# SCH_Amiga-KickSmash-32-in-system-flash_2.net
KiCad netlist of a schematic drawn in EasyEDA
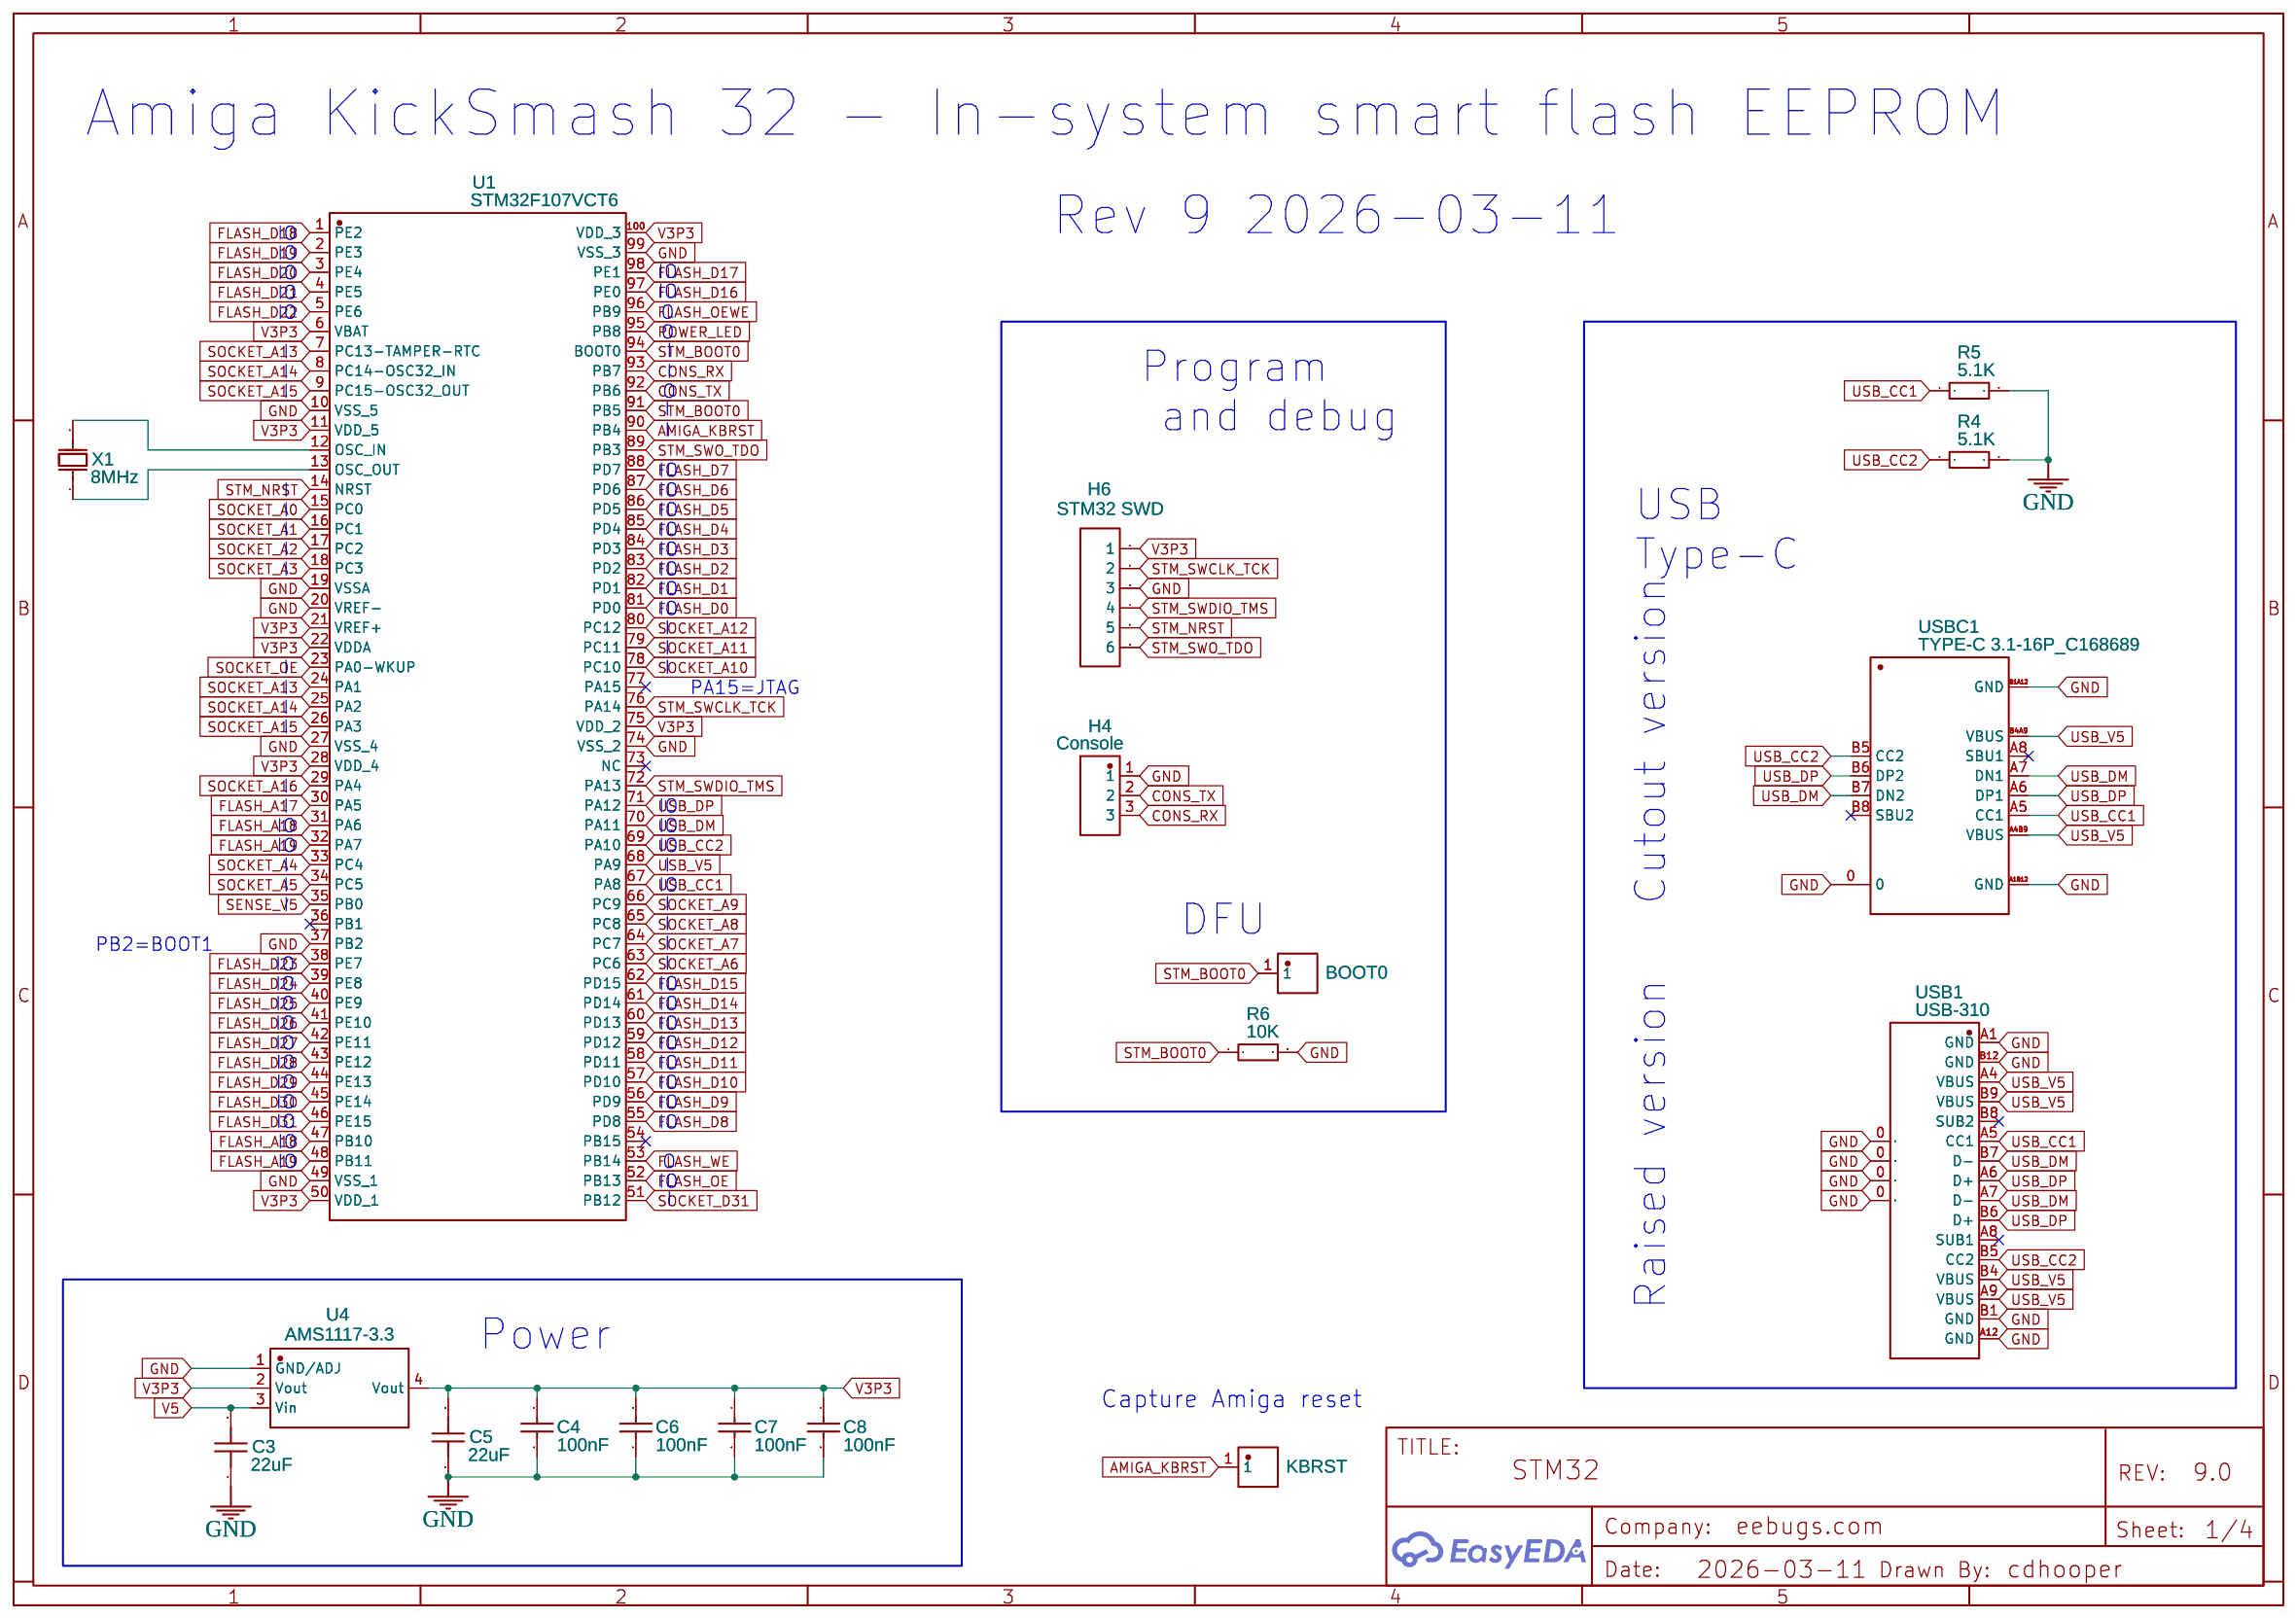
[diagram p0: STM32]
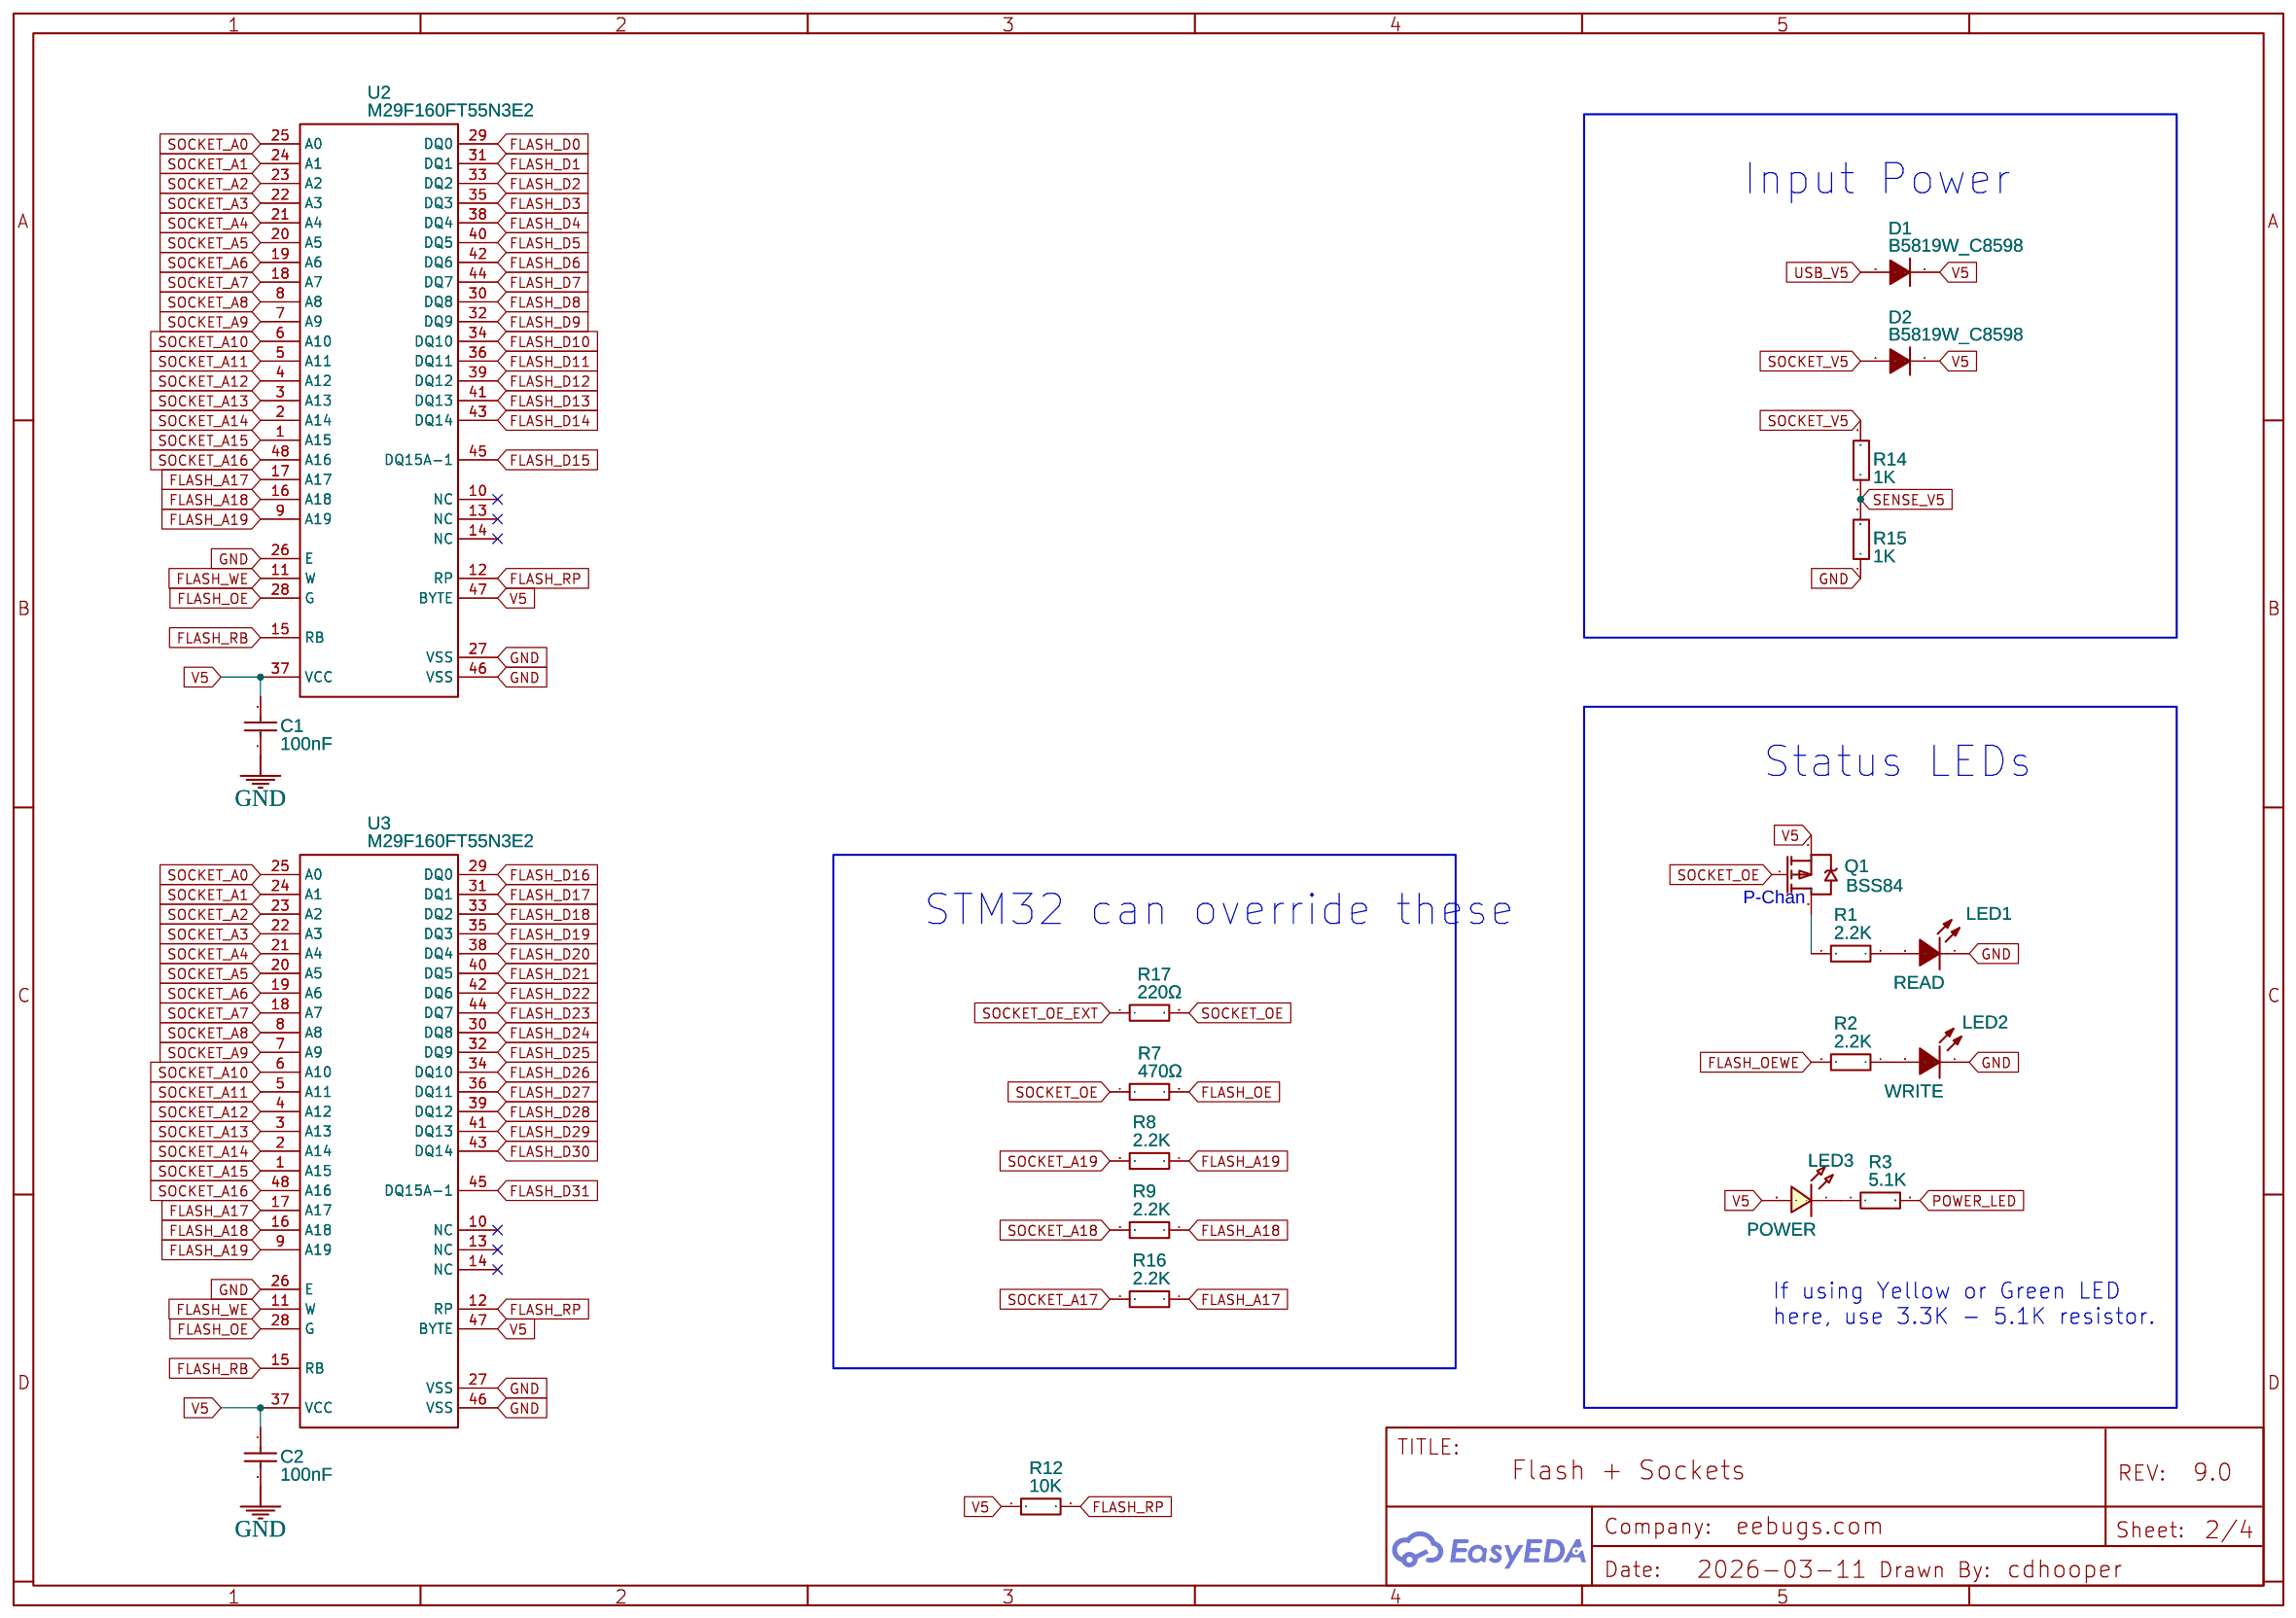
[diagram p1: Flash]
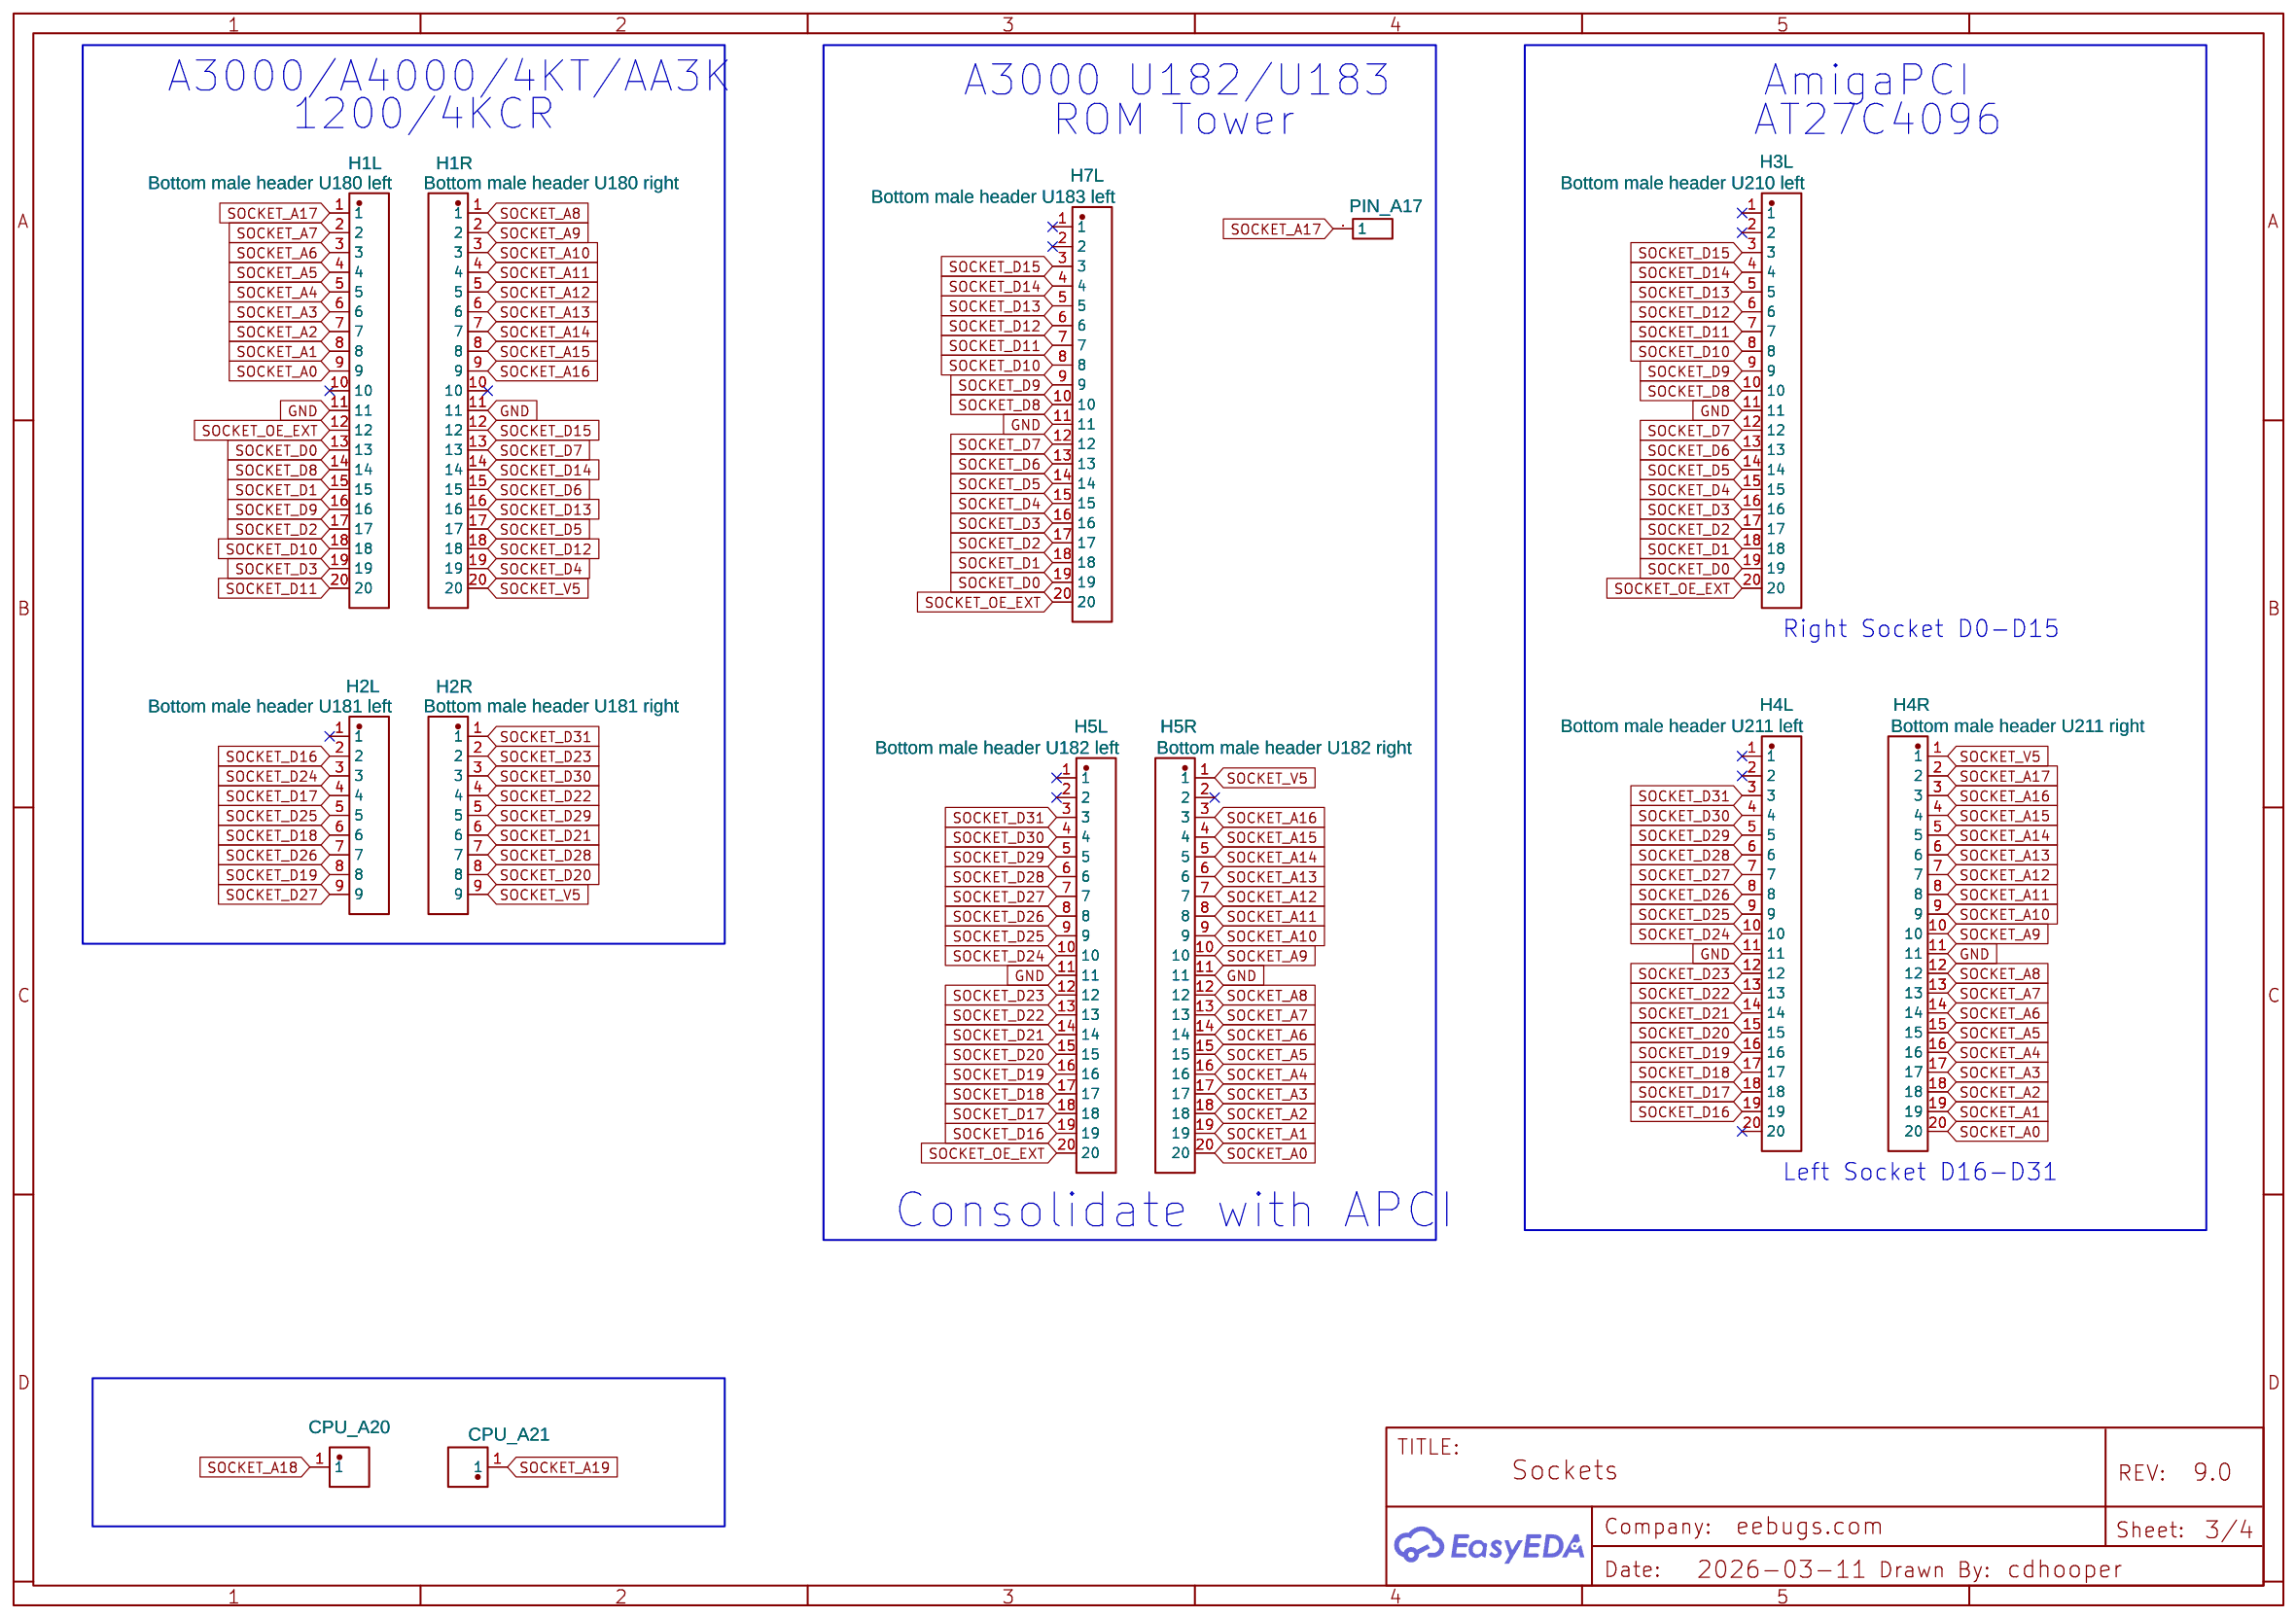
[diagram p2: Sockets]
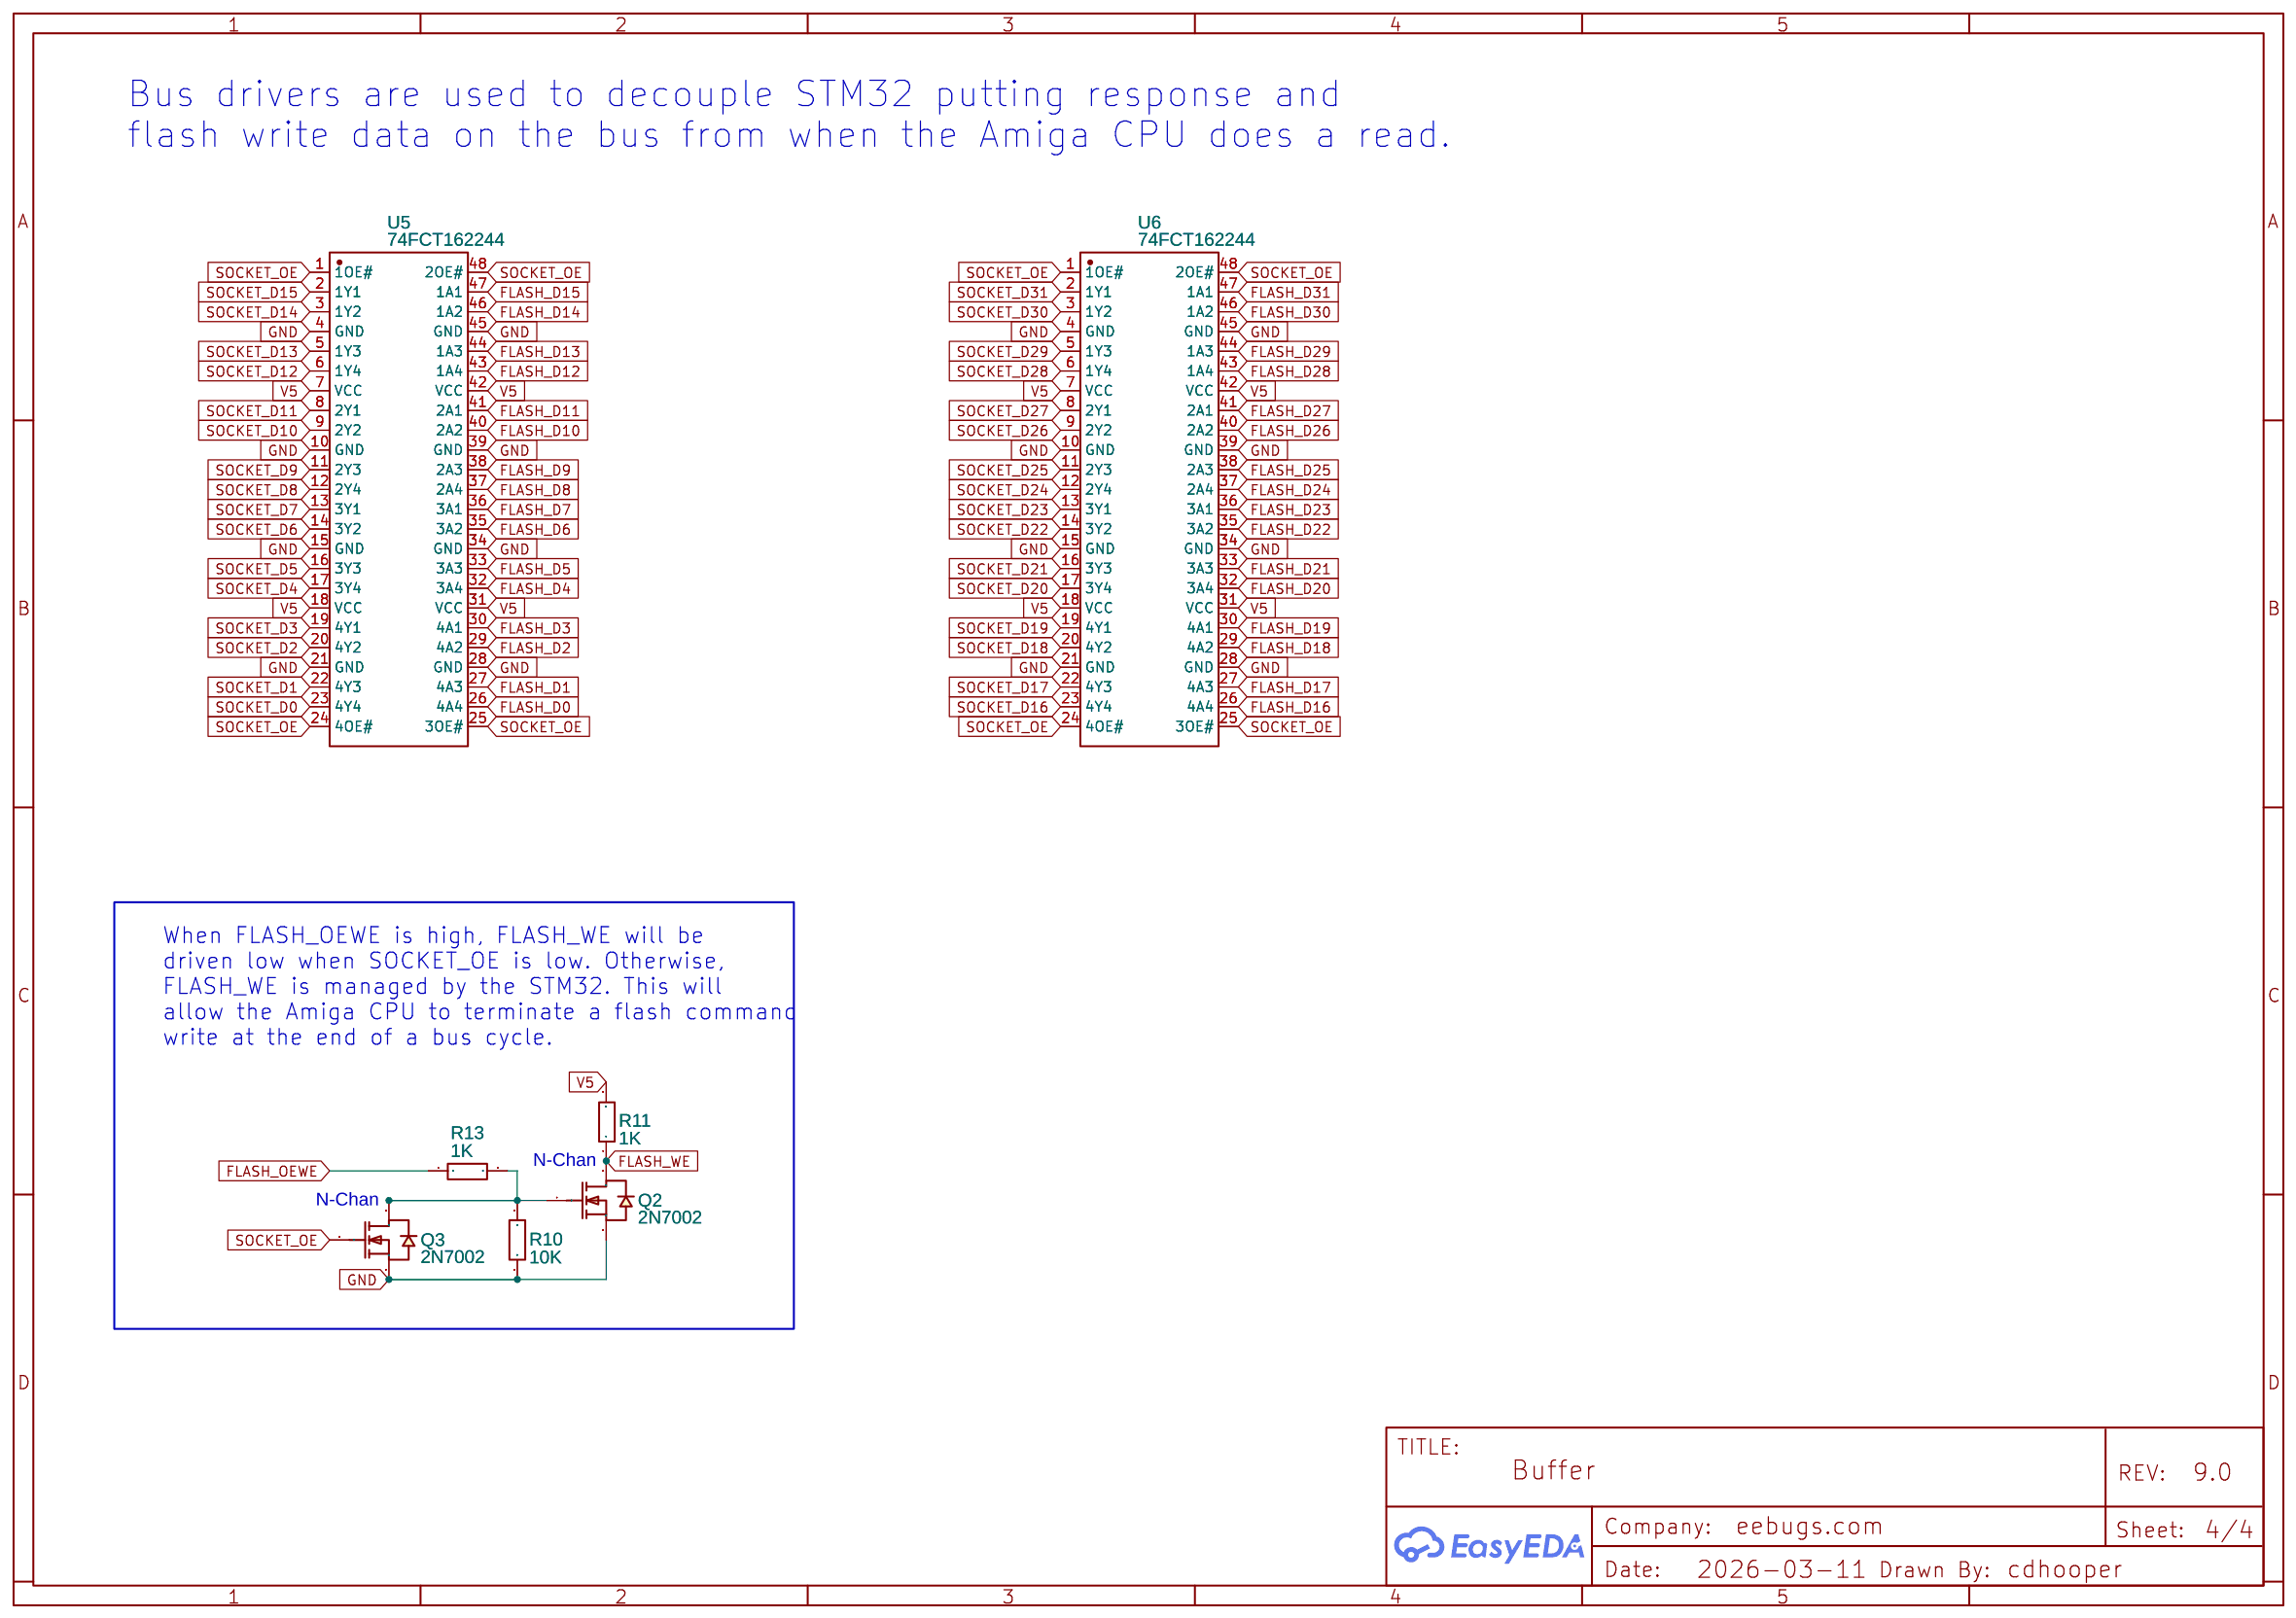
[diagram p3: Buffer]

(export (version "E")
  (design (tool "Eeschema 10.0.6"))
  (components
    (comp (ref "C3")
      (value "22uF")
      (fields (field (name "Manufacturer Part") "CL21A226MAQNNNE") (field (name "Manufacturer") "SAMSUNG"))
      (libsource (lib "") (part "CL21A226MAQNNNE"))
    )
    (comp (ref "C4")
      (value "100nF")
      (fields (field (name "Manufacturer Part") "CC0805KRX7R9BB104") (field (name "Manufacturer") "YAGEO"))
      (libsource (lib "") (part "CC0805KRX7R9BB104"))
    )
    (comp (ref "C5")
      (value "22uF")
      (fields (field (name "Manufacturer Part") "CL21A226MAQNNNE") (field (name "Manufacturer") "SAMSUNG"))
      (libsource (lib "") (part "CL21A226MAQNNNE"))
    )
    (comp (ref "C6")
      (value "100nF")
      (fields (field (name "Manufacturer Part") "CC0805KRX7R9BB104") (field (name "Manufacturer") "YAGEO"))
      (libsource (lib "") (part "CC0805KRX7R9BB104"))
    )
    (comp (ref "C7")
      (value "100nF")
      (fields (field (name "Manufacturer Part") "CC0805KRX7R9BB104") (field (name "Manufacturer") "YAGEO"))
      (libsource (lib "") (part "CC0805KRX7R9BB104"))
    )
    (comp (ref "C8")
      (value "100nF")
      (fields (field (name "Manufacturer Part") "CC0805KRX7R9BB104") (field (name "Manufacturer") "YAGEO"))
      (libsource (lib "") (part "CC0805KRX7R9BB104"))
    )
    (comp (ref "H3")
      (value "KBRST")
      (fields
        (field (name "Manufacturer Part") "X6511WR-01H-C60D30R2")
        (field (name "Manufacturer") "XKB Connection(中国星坤)")
      )
      (libsource (lib "") (part "X6511WR-01H-C30D60R2"))
    )
    (comp (ref "H4")
      (value "Console")
      (fields (field (name "Manufacturer Part") "PZ254R-11-03P") (field (name "Manufacturer") "XFCN(兴飞)"))
      (libsource (lib "") (part "PZ254R-11-03P"))
    )
    (comp (ref "H5")
      (value "BOOT0")
      (fields
        (field (name "Manufacturer Part") "X6511WR-01H-C60D30R2")
        (field (name "Manufacturer") "XKB Connection(中国星坤)")
      )
      (libsource (lib "") (part "X6511WR-01H-C30D60R2"))
    )
    (comp (ref "H6")
      (value "STM32 SWD")
      (fields (field (name "Manufacturer Part") "Female header 1*6p") (field (name "Manufacturer") "BOOMELE"))
      (libsource (lib "") (part "Unknown_555_-510"))
    )
    (comp (ref "R4")
      (value "5.1K")
      (fields (field (name "Manufacturer Part") "0805W8F5101T5E") (field (name "Manufacturer") "UniOhm"))
      (libsource (lib "") (part "0805W8F5101T5E"))
    )
    (comp (ref "R5")
      (value "5.1K")
      (fields (field (name "Manufacturer Part") "0805W8F5101T5E") (field (name "Manufacturer") "UniOhm"))
      (libsource (lib "") (part "0805W8F5101T5E"))
    )
    (comp (ref "R6")
      (value "10K")
      (fields (field (name "Manufacturer Part") "0805W8F1002T5E") (field (name "Manufacturer") "UniOhm"))
      (libsource (lib "") (part "0805W8F1002T5E"))
    )
    (comp (ref "U1")
      (value "STM32F107VCT6")
      (fields (field (name "Manufacturer") "STMicroelectronics"))
      (libsource (lib "") (part "STM32F107VCT6"))
    )
    (comp (ref "U4")
      (value "AMS1117-3.3")
      (fields (field (name "Manufacturer") "AMS"))
      (libsource (lib "") (part "AMS1117-3.3"))
    )
    (comp (ref "USB1")
      (value "USB-310")
      (fields (field (name "Manufacturer Part") "USB-310-B-SU") (field (name "Manufacturer") "HOOYA(皓宇电子)"))
      (libsource (lib "") (part "USB-310"))
    )
    (comp (ref "USBC1")
      (value "TYPE-C 3.1-16P_C168689")
      (fields (field (name "Manufacturer") "LCSC"))
      (libsource (lib "") (part "TYPE-C 3.1-16P_C168689"))
    )
    (comp (ref "X1")
      (value "8MHz")
      (fields (field (name "Manufacturer Part") "X50328MSB2GI") (field (name "Manufacturer") "YXC"))
      (libsource (lib "") (part "X50328MSB2GI"))
    )
    (comp (ref "C1")
      (value "100nF")
      (fields (field (name "Manufacturer Part") "CC0805KRX7R9BB104") (field (name "Manufacturer") "YAGEO"))
      (libsource (lib "") (part "CC0805KRX7R9BB104"))
    )
    (comp (ref "C2")
      (value "100nF")
      (fields (field (name "Manufacturer Part") "CC0805KRX7R9BB104") (field (name "Manufacturer") "YAGEO"))
      (libsource (lib "") (part "CC0805KRX7R9BB104"))
    )
    (comp (ref "D1")
      (value "B5819W_C8598")
      (fields (field (name "Manufacturer Part") "B5819W") (field (name "Manufacturer") "CJ"))
      (libsource (lib "") (part "B5819W_C8598"))
    )
    (comp (ref "D2")
      (value "B5819W_C8598")
      (fields (field (name "Manufacturer Part") "B5819W") (field (name "Manufacturer") "CJ"))
      (libsource (lib "") (part "B5819W_C8598"))
    )
    (comp (ref "LED1")
      (value "READ")
      (fields (field (name "Manufacturer Part") "17-21SUYC/TR8") (field (name "Manufacturer") "KENTO"))
      (libsource (lib "") (part "17-21SUYC/TR8"))
    )
    (comp (ref "LED2")
      (value "WRITE")
      (fields (field (name "Manufacturer Part") "0805G (Green)") (field (name "Manufacturer") "KENTO"))
      (libsource (lib "") (part "0805G (Green)"))
    )
    (comp (ref "LED3")
      (value "POWER")
      (fields
        (field (name "Manufacturer Part") "P2-0805UVTCS2-0.8T")
        (field (name "Manufacturer") "TUOZHAN(拓展光电)")
      )
      (libsource (lib "") (part "P2-0805UVTCS2-0.8T"))
    )
    (comp (ref "Q1")
      (value "BSS84")
      (fields (field (name "Manufacturer Part") "LBSS84LT1G") (field (name "Manufacturer") "LRC"))
      (libsource (lib "") (part "Unknown_905_-370"))
    )
    (comp (ref "R1")
      (value "2.2K")
      (fields (field (name "Manufacturer Part") "0805W8F2201T5E") (field (name "Manufacturer") "UniOhm"))
      (libsource (lib "") (part "0805W8F2201T5E"))
    )
    (comp (ref "R2")
      (value "2.2K")
      (fields (field (name "Manufacturer Part") "0805W8F2201T5E") (field (name "Manufacturer") "UniOhm"))
      (libsource (lib "") (part "0805W8F2201T5E"))
    )
    (comp (ref "R3")
      (value "5.1K")
      (fields (field (name "Manufacturer Part") "0805W8F5101T5E") (field (name "Manufacturer") "UniOhm"))
      (libsource (lib "") (part "0805W8F5101T5E"))
    )
    (comp (ref "R7")
      (value "470Ω")
      (fields
        (field (name "Manufacturer Part") "0805W8F4700T5E")
        (field (name "Manufacturer") "UNI-ROYAL(厚声)")
      )
      (libsource (lib "") (part "0805W8F4700T5E"))
    )
    (comp (ref "R8")
      (value "2.2K")
      (fields (field (name "Manufacturer Part") "0805W8F2201T5E") (field (name "Manufacturer") "UniOhm"))
      (libsource (lib "") (part "0805W8F2201T5E"))
    )
    (comp (ref "R9")
      (value "2.2K")
      (fields (field (name "Manufacturer Part") "0805W8F2201T5E") (field (name "Manufacturer") "UniOhm"))
      (libsource (lib "") (part "0805W8F2201T5E"))
    )
    (comp (ref "R12")
      (value "10K")
      (fields (field (name "Manufacturer Part") "0805W8F1002T5E") (field (name "Manufacturer") "UniOhm"))
      (libsource (lib "") (part "0805W8F1002T5E"))
    )
    (comp (ref "R14")
      (value "1K")
      (fields (field (name "Manufacturer Part") "0805W8F1001T5E") (field (name "Manufacturer") "UniOhm"))
      (libsource (lib "") (part "0805W8F1001T5E"))
    )
    (comp (ref "R15")
      (value "1K")
      (fields (field (name "Manufacturer Part") "0805W8F1001T5E") (field (name "Manufacturer") "UniOhm"))
      (libsource (lib "") (part "0805W8F1001T5E"))
    )
    (comp (ref "R16")
      (value "2.2K")
      (fields (field (name "Manufacturer Part") "0805W8F2201T5E") (field (name "Manufacturer") "UniOhm"))
      (libsource (lib "") (part "0805W8F2201T5E"))
    )
    (comp (ref "R17")
      (value "220Ω")
      (fields
        (field (name "Manufacturer Part") "0805W8F2200T5E")
        (field (name "Manufacturer") "UNI-ROYAL(厚声)")
      )
      (libsource (lib "") (part "0805W8F2200T5E"))
    )
    (comp (ref "U2") (value "M29F160FT55N3E2") (libsource (lib "") (part "M29F160FT55N3E2")))
    (comp (ref "U3") (value "M29F160FT55N3E2") (libsource (lib "") (part "M29F160FT55N3E2")))
    (comp (ref "H1L")
      (value "Bottom male header U180 left")
      (fields (field (name "Manufacturer Part") "PZ254-1-20-Z-C") (field (name "Manufacturer") "HCTL(华灿天禄)"))
      (libsource (lib "") (part "PZ254-1-20-Z-C_1"))
    )
    (comp (ref "H1R")
      (value "Bottom male header U180 right")
      (fields (field (name "Manufacturer Part") "PZ254-1-20-Z-C") (field (name "Manufacturer") "HCTL(华灿天禄)"))
      (libsource (lib "") (part "PZ254-1-20-Z-C"))
    )
    (comp (ref "H2L")
      (value "Bottom male header U181 left")
      (fields (field (name "Manufacturer Part") "PZ254-1-09-Z-C") (field (name "Manufacturer") "HCTL(华灿天禄)"))
      (libsource (lib "") (part "PZ254-1-09-Z-C_1"))
    )
    (comp (ref "H2R")
      (value "Bottom male header U181 right")
      (fields (field (name "Manufacturer Part") "PZ254-1-09-Z-C") (field (name "Manufacturer") "HCTL(华灿天禄)"))
      (libsource (lib "") (part "PZ254-1-09-Z-C"))
    )
    (comp (ref "H3L")
      (value "Bottom male header U210 left")
      (fields (field (name "Manufacturer Part") "2.54mm 1*20PHeader") (field (name "Manufacturer") "BOOMELE"))
      (libsource (lib "") (part "Header-Male-2.54_1x20_2"))
    )
    (comp (ref "H4L")
      (value "Bottom male header U211 left")
      (fields (field (name "Manufacturer Part") "2.54mm 1*20PHeader") (field (name "Manufacturer") "BOOMELE"))
      (libsource (lib "") (part "Header-Male-2.54_1x20"))
    )
    (comp (ref "H4R")
      (value "Bottom male header U211 right")
      (fields (field (name "Manufacturer Part") "2.54mm 1*20PHeader") (field (name "Manufacturer") "BOOMELE"))
      (libsource (lib "") (part "Header-Male-2.54_1x20_1"))
    )
    (comp (ref "H5L")
      (value "Bottom male header U182 left")
      (fields (field (name "Manufacturer Part") "2.54mm 1*20PHeader") (field (name "Manufacturer") "BOOMELE"))
      (libsource (lib "") (part "Header-Male-2.54_1x20_3"))
    )
    (comp (ref "H5R")
      (value "Bottom male header U182 right")
      (fields (field (name "Manufacturer Part") "2.54mm 1*20PHeader") (field (name "Manufacturer") "BOOMELE"))
      (libsource (lib "") (part "Header-Male-2.54_1x20_4"))
    )
    (comp (ref "H7")
      (value "CPU_A20")
      (fields
        (field (name "Manufacturer Part") "X6511WR-01H-C60D30R2")
        (field (name "Manufacturer") "XKB Connection(中国星坤)")
      )
      (libsource (lib "") (part "X6511WR-01H-C30D60R2_1"))
    )
    (comp (ref "H7L")
      (value "Bottom male header U183 left")
      (fields (field (name "Manufacturer Part") "2.54mm 1*20PHeader") (field (name "Manufacturer") "BOOMELE"))
      (libsource (lib "") (part "Header-Male-2.54_1x20_5"))
    )
    (comp (ref "H8")
      (value "CPU_A21")
      (fields
        (field (name "Manufacturer Part") "X6511WR-01H-C60D30R2")
        (field (name "Manufacturer") "XKB Connection(中国星坤)")
      )
      (libsource (lib "") (part "X6511WR-01H-C30D60R2"))
    )
    (comp (ref "H9")
      (value "PIN_A17")
      (fields
        (field (name "Manufacturer Part") "Header-Male-2.54_1x1")
        (field (name "Manufacturer") "ReliaPro")
      )
      (libsource (lib "") (part "Header-Male-2.54_1x1"))
    )
    (comp (ref "Q2")
      (value "2N7002")
      (fields (field (name "Manufacturer") "CJ(江苏长电/长晶)"))
      (libsource (lib "") (part "AO3400A"))
    )
    (comp (ref "Q3")
      (value "2N7002")
      (fields (field (name "Manufacturer") "CJ(江苏长电/长晶)"))
      (libsource (lib "") (part "AO3400A"))
    )
    (comp (ref "R10")
      (value "10K")
      (fields (field (name "Manufacturer Part") "0805W8F1002T5E") (field (name "Manufacturer") "UniOhm"))
      (libsource (lib "") (part "0805W8F1002T5E"))
    )
    (comp (ref "R11")
      (value "1K")
      (fields (field (name "Manufacturer Part") "0805W8F1001T5E") (field (name "Manufacturer") "UniOhm"))
      (libsource (lib "") (part "0805W8F1001T5E_1"))
    )
    (comp (ref "R13")
      (value "1K")
      (fields (field (name "Manufacturer Part") "0805W8F1001T5E") (field (name "Manufacturer") "UniOhm"))
      (libsource (lib "") (part "0805W8F1001T5E"))
    )
    (comp (ref "U5")
      (value "74FCT162244")
      (fields
        (field (name "Manufacturer Part") "74FCT162244CTPAG")
        (field (name "Manufacturer") "RENESAS(瑞萨)/IDT")
      )
      (libsource (lib "") (part "74FCT162244CTPAG"))
    )
    (comp (ref "U6")
      (value "74FCT162244")
      (fields
        (field (name "Manufacturer Part") "74FCT162244CTPAG")
        (field (name "Manufacturer") "RENESAS(瑞萨)/IDT")
      )
      (libsource (lib "") (part "74FCT162244CTPAG"))
    )
  )
  (nets
    (net (code "1") (name "AMIGA_KBRST") (class "Default")
      (node (ref "H3") (pin "1") (pinfunction "1_1") (pintype "unspecified"))
      (node (ref "U1") (pin "90") (pinfunction "PB4_90") (pintype "unspecified"))
    )
    (net (code "2") (name "CONS_RX") (class "Default")
      (node (ref "H4") (pin "3") (pinfunction "3_3") (pintype "unspecified"))
      (node (ref "U1") (pin "93") (pinfunction "PB7_93") (pintype "unspecified"))
    )
    (net (code "3") (name "CONS_TX") (class "Default")
      (node (ref "H4") (pin "2") (pinfunction "2_2") (pintype "unspecified"))
      (node (ref "U1") (pin "92") (pinfunction "PB6_92") (pintype "unspecified"))
    )
    (net (code "4") (name "FLASH_A17") (class "Default")
      (node (ref "R16") (pin "1") (pinfunction "1_1") (pintype "input"))
      (node (ref "U1") (pin "30") (pinfunction "PA5_30") (pintype "unspecified"))
      (node (ref "U2") (pin "17") (pinfunction "A17_17") (pintype "unspecified"))
      (node (ref "U3") (pin "17") (pinfunction "A17_17") (pintype "unspecified"))
    )
    (net (code "5") (name "FLASH_A18") (class "Default")
      (node (ref "R9") (pin "1") (pinfunction "1_1") (pintype "input"))
      (node (ref "U1") (pin "31") (pinfunction "PA6_31") (pintype "unspecified"))
      (node (ref "U1") (pin "47") (pinfunction "PB10_47") (pintype "unspecified"))
      (node (ref "U2") (pin "16") (pinfunction "A18_16") (pintype "unspecified"))
      (node (ref "U3") (pin "16") (pinfunction "A18_16") (pintype "unspecified"))
    )
    (net (code "6") (name "FLASH_A19") (class "Default")
      (node (ref "R8") (pin "1") (pinfunction "1_1") (pintype "input"))
      (node (ref "U1") (pin "32") (pinfunction "PA7_32") (pintype "unspecified"))
      (node (ref "U1") (pin "48") (pinfunction "PB11_48") (pintype "unspecified"))
      (node (ref "U2") (pin "9") (pinfunction "A19_9") (pintype "unspecified"))
      (node (ref "U3") (pin "9") (pinfunction "A19_9") (pintype "unspecified"))
    )
    (net (code "7") (name "FLASH_D0") (class "Default")
      (node (ref "U1") (pin "81") (pinfunction "PD0_81") (pintype "unspecified"))
      (node (ref "U2") (pin "29") (pinfunction "DQ0_29") (pintype "bidirectional"))
      (node (ref "U5") (pin "26") (pinfunction "4A4_26") (pintype "unspecified"))
    )
    (net (code "8") (name "FLASH_D1") (class "Default")
      (node (ref "U1") (pin "82") (pinfunction "PD1_82") (pintype "unspecified"))
      (node (ref "U2") (pin "31") (pinfunction "DQ1_31") (pintype "bidirectional"))
      (node (ref "U5") (pin "27") (pinfunction "4A3_27") (pintype "unspecified"))
    )
    (net (code "9") (name "FLASH_D2") (class "Default")
      (node (ref "U1") (pin "83") (pinfunction "PD2_83") (pintype "unspecified"))
      (node (ref "U2") (pin "33") (pinfunction "DQ2_33") (pintype "bidirectional"))
      (node (ref "U5") (pin "29") (pinfunction "4A2_29") (pintype "unspecified"))
    )
    (net (code "10") (name "FLASH_D3") (class "Default")
      (node (ref "U1") (pin "84") (pinfunction "PD3_84") (pintype "unspecified"))
      (node (ref "U2") (pin "35") (pinfunction "DQ3_35") (pintype "bidirectional"))
      (node (ref "U5") (pin "30") (pinfunction "4A1_30") (pintype "unspecified"))
    )
    (net (code "11") (name "FLASH_D4") (class "Default")
      (node (ref "U1") (pin "85") (pinfunction "PD4_85") (pintype "unspecified"))
      (node (ref "U2") (pin "38") (pinfunction "DQ4_38") (pintype "bidirectional"))
      (node (ref "U5") (pin "32") (pinfunction "3A4_32") (pintype "unspecified"))
    )
    (net (code "12") (name "FLASH_D5") (class "Default")
      (node (ref "U1") (pin "86") (pinfunction "PD5_86") (pintype "unspecified"))
      (node (ref "U2") (pin "40") (pinfunction "DQ5_40") (pintype "bidirectional"))
      (node (ref "U5") (pin "33") (pinfunction "3A3_33") (pintype "unspecified"))
    )
    (net (code "13") (name "FLASH_D6") (class "Default")
      (node (ref "U1") (pin "87") (pinfunction "PD6_87") (pintype "unspecified"))
      (node (ref "U2") (pin "42") (pinfunction "DQ6_42") (pintype "bidirectional"))
      (node (ref "U5") (pin "35") (pinfunction "3A2_35") (pintype "unspecified"))
    )
    (net (code "14") (name "FLASH_D7") (class "Default")
      (node (ref "U1") (pin "88") (pinfunction "PD7_88") (pintype "unspecified"))
      (node (ref "U2") (pin "44") (pinfunction "DQ7_44") (pintype "bidirectional"))
      (node (ref "U5") (pin "36") (pinfunction "3A1_36") (pintype "unspecified"))
    )
    (net (code "15") (name "FLASH_D8") (class "Default")
      (node (ref "U1") (pin "55") (pinfunction "PD8_55") (pintype "unspecified"))
      (node (ref "U2") (pin "30") (pinfunction "DQ8_30") (pintype "bidirectional"))
      (node (ref "U5") (pin "37") (pinfunction "2A4_37") (pintype "unspecified"))
    )
    (net (code "16") (name "FLASH_D9") (class "Default")
      (node (ref "U1") (pin "56") (pinfunction "PD9_56") (pintype "unspecified"))
      (node (ref "U2") (pin "32") (pinfunction "DQ9_32") (pintype "bidirectional"))
      (node (ref "U5") (pin "38") (pinfunction "2A3_38") (pintype "unspecified"))
    )
    (net (code "17") (name "FLASH_D10") (class "Default")
      (node (ref "U1") (pin "57") (pinfunction "PD10_57") (pintype "unspecified"))
      (node (ref "U2") (pin "34") (pinfunction "DQ10_34") (pintype "bidirectional"))
      (node (ref "U5") (pin "40") (pinfunction "2A2_40") (pintype "unspecified"))
    )
    (net (code "18") (name "FLASH_D11") (class "Default")
      (node (ref "U1") (pin "58") (pinfunction "PD11_58") (pintype "unspecified"))
      (node (ref "U2") (pin "36") (pinfunction "DQ11_36") (pintype "bidirectional"))
      (node (ref "U5") (pin "41") (pinfunction "2A1_41") (pintype "unspecified"))
    )
    (net (code "19") (name "FLASH_D12") (class "Default")
      (node (ref "U1") (pin "59") (pinfunction "PD12_59") (pintype "unspecified"))
      (node (ref "U2") (pin "39") (pinfunction "DQ12_39") (pintype "bidirectional"))
      (node (ref "U5") (pin "43") (pinfunction "1A4_43") (pintype "unspecified"))
    )
    (net (code "20") (name "FLASH_D13") (class "Default")
      (node (ref "U1") (pin "60") (pinfunction "PD13_60") (pintype "unspecified"))
      (node (ref "U2") (pin "41") (pinfunction "DQ13_41") (pintype "bidirectional"))
      (node (ref "U5") (pin "44") (pinfunction "1A3_44") (pintype "unspecified"))
    )
    (net (code "21") (name "FLASH_D14") (class "Default")
      (node (ref "U1") (pin "61") (pinfunction "PD14_61") (pintype "unspecified"))
      (node (ref "U2") (pin "43") (pinfunction "DQ14_43") (pintype "bidirectional"))
      (node (ref "U5") (pin "46") (pinfunction "1A2_46") (pintype "unspecified"))
    )
    (net (code "22") (name "FLASH_D15") (class "Default")
      (node (ref "U1") (pin "62") (pinfunction "PD15_62") (pintype "unspecified"))
      (node (ref "U2") (pin "45") (pinfunction "DQ15A-1_45") (pintype "bidirectional"))
      (node (ref "U5") (pin "47") (pinfunction "1A1_47") (pintype "unspecified"))
    )
    (net (code "23") (name "FLASH_D16") (class "Default")
      (node (ref "U1") (pin "97") (pinfunction "PE0_97") (pintype "unspecified"))
      (node (ref "U3") (pin "29") (pinfunction "DQ0_29") (pintype "bidirectional"))
      (node (ref "U6") (pin "26") (pinfunction "4A4_26") (pintype "unspecified"))
    )
    (net (code "24") (name "FLASH_D17") (class "Default")
      (node (ref "U1") (pin "98") (pinfunction "PE1_98") (pintype "unspecified"))
      (node (ref "U3") (pin "31") (pinfunction "DQ1_31") (pintype "bidirectional"))
      (node (ref "U6") (pin "27") (pinfunction "4A3_27") (pintype "unspecified"))
    )
    (net (code "25") (name "FLASH_D18") (class "Default")
      (node (ref "U1") (pin "1") (pinfunction "PE2_1") (pintype "unspecified"))
      (node (ref "U3") (pin "33") (pinfunction "DQ2_33") (pintype "bidirectional"))
      (node (ref "U6") (pin "29") (pinfunction "4A2_29") (pintype "unspecified"))
    )
    (net (code "26") (name "FLASH_D19") (class "Default")
      (node (ref "U1") (pin "2") (pinfunction "PE3_2") (pintype "unspecified"))
      (node (ref "U3") (pin "35") (pinfunction "DQ3_35") (pintype "bidirectional"))
      (node (ref "U6") (pin "30") (pinfunction "4A1_30") (pintype "unspecified"))
    )
    (net (code "27") (name "FLASH_D20") (class "Default")
      (node (ref "U1") (pin "3") (pinfunction "PE4_3") (pintype "unspecified"))
      (node (ref "U3") (pin "38") (pinfunction "DQ4_38") (pintype "bidirectional"))
      (node (ref "U6") (pin "32") (pinfunction "3A4_32") (pintype "unspecified"))
    )
    (net (code "28") (name "FLASH_D21") (class "Default")
      (node (ref "U1") (pin "4") (pinfunction "PE5_4") (pintype "unspecified"))
      (node (ref "U3") (pin "40") (pinfunction "DQ5_40") (pintype "bidirectional"))
      (node (ref "U6") (pin "33") (pinfunction "3A3_33") (pintype "unspecified"))
    )
    (net (code "29") (name "FLASH_D22") (class "Default")
      (node (ref "U1") (pin "5") (pinfunction "PE6_5") (pintype "unspecified"))
      (node (ref "U3") (pin "42") (pinfunction "DQ6_42") (pintype "bidirectional"))
      (node (ref "U6") (pin "35") (pinfunction "3A2_35") (pintype "unspecified"))
    )
    (net (code "30") (name "FLASH_D23") (class "Default")
      (node (ref "U1") (pin "38") (pinfunction "PE7_38") (pintype "unspecified"))
      (node (ref "U3") (pin "44") (pinfunction "DQ7_44") (pintype "bidirectional"))
      (node (ref "U6") (pin "36") (pinfunction "3A1_36") (pintype "unspecified"))
    )
    (net (code "31") (name "FLASH_D24") (class "Default")
      (node (ref "U1") (pin "39") (pinfunction "PE8_39") (pintype "unspecified"))
      (node (ref "U3") (pin "30") (pinfunction "DQ8_30") (pintype "bidirectional"))
      (node (ref "U6") (pin "37") (pinfunction "2A4_37") (pintype "unspecified"))
    )
    (net (code "32") (name "FLASH_D25") (class "Default")
      (node (ref "U1") (pin "40") (pinfunction "PE9_40") (pintype "unspecified"))
      (node (ref "U3") (pin "32") (pinfunction "DQ9_32") (pintype "bidirectional"))
      (node (ref "U6") (pin "38") (pinfunction "2A3_38") (pintype "unspecified"))
    )
    (net (code "33") (name "FLASH_D26") (class "Default")
      (node (ref "U1") (pin "41") (pinfunction "PE10_41") (pintype "unspecified"))
      (node (ref "U3") (pin "34") (pinfunction "DQ10_34") (pintype "bidirectional"))
      (node (ref "U6") (pin "40") (pinfunction "2A2_40") (pintype "unspecified"))
    )
    (net (code "34") (name "FLASH_D27") (class "Default")
      (node (ref "U1") (pin "42") (pinfunction "PE11_42") (pintype "unspecified"))
      (node (ref "U3") (pin "36") (pinfunction "DQ11_36") (pintype "bidirectional"))
      (node (ref "U6") (pin "41") (pinfunction "2A1_41") (pintype "unspecified"))
    )
    (net (code "35") (name "FLASH_D28") (class "Default")
      (node (ref "U1") (pin "43") (pinfunction "PE12_43") (pintype "unspecified"))
      (node (ref "U3") (pin "39") (pinfunction "DQ12_39") (pintype "bidirectional"))
      (node (ref "U6") (pin "43") (pinfunction "1A4_43") (pintype "unspecified"))
    )
    (net (code "36") (name "FLASH_D29") (class "Default")
      (node (ref "U1") (pin "44") (pinfunction "PE13_44") (pintype "unspecified"))
      (node (ref "U3") (pin "41") (pinfunction "DQ13_41") (pintype "bidirectional"))
      (node (ref "U6") (pin "44") (pinfunction "1A3_44") (pintype "unspecified"))
    )
    (net (code "37") (name "FLASH_D30") (class "Default")
      (node (ref "U1") (pin "45") (pinfunction "PE14_45") (pintype "unspecified"))
      (node (ref "U3") (pin "43") (pinfunction "DQ14_43") (pintype "bidirectional"))
      (node (ref "U6") (pin "46") (pinfunction "1A2_46") (pintype "unspecified"))
    )
    (net (code "38") (name "FLASH_D31") (class "Default")
      (node (ref "U1") (pin "46") (pinfunction "PE15_46") (pintype "unspecified"))
      (node (ref "U3") (pin "45") (pinfunction "DQ15A-1_45") (pintype "bidirectional"))
      (node (ref "U6") (pin "47") (pinfunction "1A1_47") (pintype "unspecified"))
    )
    (net (code "39") (name "FLASH_OE") (class "Default")
      (node (ref "R7") (pin "2") (pinfunction "2_2") (pintype "input"))
      (node (ref "U1") (pin "52") (pinfunction "PB13_52") (pintype "unspecified"))
      (node (ref "U2") (pin "28") (pinfunction "G_28") (pintype "unspecified"))
      (node (ref "U3") (pin "28") (pinfunction "G_28") (pintype "unspecified"))
    )
    (net (code "40") (name "FLASH_OEWE") (class "Default")
      (node (ref "R13") (pin "1") (pinfunction "1_1") (pintype "input"))
      (node (ref "R2") (pin "2") (pinfunction "2_2") (pintype "input"))
      (node (ref "U1") (pin "96") (pinfunction "PB9_96") (pintype "unspecified"))
    )
    (net (code "41") (name "FLASH_RB") (class "Default")
      (node (ref "U2") (pin "15") (pinfunction "RB_15") (pintype "unspecified"))
      (node (ref "U3") (pin "15") (pinfunction "RB_15") (pintype "unspecified"))
    )
    (net (code "42") (name "FLASH_RP") (class "Default")
      (node (ref "R12") (pin "2") (pinfunction "2_2") (pintype "input"))
      (node (ref "U2") (pin "12") (pinfunction "RP_12") (pintype "unspecified"))
      (node (ref "U3") (pin "12") (pinfunction "RP_12") (pintype "unspecified"))
    )
    (net (code "43") (name "FLASH_WE") (class "Default")
      (node (ref "Q2") (pin "3") (pinfunction "D_3") (pintype "unspecified"))
      (node (ref "R11") (pin "1") (pinfunction "1_1") (pintype "input"))
      (node (ref "U1") (pin "53") (pinfunction "PB14_53") (pintype "unspecified"))
      (node (ref "U2") (pin "11") (pinfunction "W_11") (pintype "unspecified"))
      (node (ref "U3") (pin "11") (pinfunction "W_11") (pintype "unspecified"))
    )
    (net (code "44") (name "GND") (class "Default")
      (node (ref "C1") (pin "2") (pinfunction "2_2") (pintype "input"))
      (node (ref "C2") (pin "2") (pinfunction "2_2") (pintype "input"))
      (node (ref "C3") (pin "1") (pinfunction "1_1") (pintype "unspecified"))
      (node (ref "C4") (pin "2") (pinfunction "2_2") (pintype "input"))
      (node (ref "C5") (pin "1") (pinfunction "1_1") (pintype "unspecified"))
      (node (ref "C6") (pin "2") (pinfunction "2_2") (pintype "input"))
      (node (ref "C7") (pin "2") (pinfunction "2_2") (pintype "input"))
      (node (ref "C8") (pin "2") (pinfunction "2_2") (pintype "input"))
      (node (ref "H1L") (pin "11") (pinfunction "11_11") (pintype "unspecified"))
      (node (ref "H1R") (pin "11") (pinfunction "11_11") (pintype "unspecified"))
      (node (ref "H3L") (pin "11") (pinfunction "11_11") (pintype "unspecified"))
      (node (ref "H4") (pin "1") (pinfunction "1_1") (pintype "unspecified"))
      (node (ref "H4L") (pin "11") (pinfunction "11_11") (pintype "unspecified"))
      (node (ref "H4R") (pin "11") (pinfunction "11_11") (pintype "unspecified"))
      (node (ref "H5L") (pin "11") (pinfunction "11_11") (pintype "unspecified"))
      (node (ref "H5R") (pin "11") (pinfunction "11_11") (pintype "unspecified"))
      (node (ref "H6") (pin "3") (pinfunction "3_3") (pintype "input"))
      (node (ref "H7L") (pin "11") (pinfunction "11_11") (pintype "unspecified"))
      (node (ref "LED1") (pin "1") (pinfunction "-_1") (pintype "unspecified"))
      (node (ref "LED2") (pin "1") (pinfunction "K_1") (pintype "unspecified"))
      (node (ref "Q2") (pin "2") (pinfunction "S_2") (pintype "unspecified"))
      (node (ref "Q3") (pin "2") (pinfunction "S_2") (pintype "unspecified"))
      (node (ref "R10") (pin "2") (pinfunction "2_2") (pintype "input"))
      (node (ref "R15") (pin "1") (pinfunction "1_1") (pintype "input"))
      (node (ref "R4") (pin "2") (pinfunction "2_2") (pintype "input"))
      (node (ref "R5") (pin "2") (pinfunction "2_2") (pintype "input"))
      (node (ref "R6") (pin "2") (pinfunction "2_2") (pintype "input"))
      (node (ref "U1") (pin "10") (pinfunction "VSS_5_10") (pintype "unspecified"))
      (node (ref "U1") (pin "19") (pinfunction "VSSA_19") (pintype "unspecified"))
      (node (ref "U1") (pin "20") (pinfunction "VREF-_20") (pintype "unspecified"))
      (node (ref "U1") (pin "27") (pinfunction "VSS_4_27") (pintype "unspecified"))
      (node (ref "U1") (pin "37") (pinfunction "PB2_37") (pintype "unspecified"))
      (node (ref "U1") (pin "49") (pinfunction "VSS_1_49") (pintype "unspecified"))
      (node (ref "U1") (pin "74") (pinfunction "VSS_2_74") (pintype "unspecified"))
      (node (ref "U1") (pin "99") (pinfunction "VSS_3_99") (pintype "unspecified"))
      (node (ref "U2") (pin "26") (pinfunction "E_26") (pintype "unspecified"))
      (node (ref "U2") (pin "27") (pinfunction "VSS_27") (pintype "passive"))
      (node (ref "U2") (pin "46") (pinfunction "VSS_46") (pintype "passive"))
      (node (ref "U3") (pin "26") (pinfunction "E_26") (pintype "unspecified"))
      (node (ref "U3") (pin "27") (pinfunction "VSS_27") (pintype "passive"))
      (node (ref "U3") (pin "46") (pinfunction "VSS_46") (pintype "passive"))
      (node (ref "U4") (pin "1") (pinfunction "GND/ADJ_1") (pintype "unspecified"))
      (node (ref "U5") (pin "10") (pinfunction "GND_10") (pintype "unspecified"))
      (node (ref "U5") (pin "15") (pinfunction "GND_15") (pintype "unspecified"))
      (node (ref "U5") (pin "21") (pinfunction "GND_21") (pintype "unspecified"))
      (node (ref "U5") (pin "28") (pinfunction "GND_28") (pintype "unspecified"))
      (node (ref "U5") (pin "34") (pinfunction "GND_34") (pintype "unspecified"))
      (node (ref "U5") (pin "39") (pinfunction "GND_39") (pintype "unspecified"))
      (node (ref "U5") (pin "4") (pinfunction "GND_4") (pintype "unspecified"))
      (node (ref "U5") (pin "45") (pinfunction "GND_45") (pintype "unspecified"))
      (node (ref "U6") (pin "10") (pinfunction "GND_10") (pintype "unspecified"))
      (node (ref "U6") (pin "15") (pinfunction "GND_15") (pintype "unspecified"))
      (node (ref "U6") (pin "21") (pinfunction "GND_21") (pintype "unspecified"))
      (node (ref "U6") (pin "28") (pinfunction "GND_28") (pintype "unspecified"))
      (node (ref "U6") (pin "34") (pinfunction "GND_34") (pintype "unspecified"))
      (node (ref "U6") (pin "39") (pinfunction "GND_39") (pintype "unspecified"))
      (node (ref "U6") (pin "4") (pinfunction "GND_4") (pintype "unspecified"))
      (node (ref "U6") (pin "45") (pinfunction "GND_45") (pintype "unspecified"))
      (node (ref "USB1") (pin "0") (pinfunction "0_0") (pintype "unspecified"))
      (node (ref "USB1") (pin "A1") (pinfunction "GND_A1") (pintype "unspecified"))
      (node (ref "USB1") (pin "A12") (pinfunction "GND_A12") (pintype "unspecified"))
      (node (ref "USB1") (pin "B1") (pinfunction "GND_B1") (pintype "unspecified"))
      (node (ref "USB1") (pin "B12") (pinfunction "GND_B12") (pintype "unspecified"))
      (node (ref "USBC1") (pin "0") (pinfunction "0_0") (pintype "unspecified"))
      (node (ref "USBC1") (pin "A1B12") (pinfunction "GND_A1B12") (pintype "unspecified"))
      (node (ref "USBC1") (pin "B1A12") (pinfunction "GND_B1A12") (pintype "unspecified"))
    )
    (net (code "45") (name "Net-(LED1-+)") (class "Default")
      (node (ref "LED1") (pin "2") (pinfunction "+_2") (pintype "unspecified"))
      (node (ref "R1") (pin "1") (pinfunction "1_1") (pintype "input"))
    )
    (net (code "46") (name "Net-(LED2-A)") (class "Default")
      (node (ref "LED2") (pin "2") (pinfunction "A_2") (pintype "unspecified"))
      (node (ref "R2") (pin "1") (pinfunction "1_1") (pintype "input"))
    )
    (net (code "47") (name "Net-(LED3--)") (class "Default")
      (node (ref "LED3") (pin "1") (pinfunction "-_1") (pintype "unspecified"))
      (node (ref "R3") (pin "1") (pinfunction "1_1") (pintype "input"))
    )
    (net (code "48") (name "Net-(Q1-D)") (class "Default")
      (node (ref "Q1") (pin "3") (pinfunction "D_3") (pintype "unspecified"))
      (node (ref "R1") (pin "2") (pinfunction "2_2") (pintype "input"))
    )
    (net (code "49") (name "Net-(Q2-G)") (class "Default")
      (node (ref "Q2") (pin "1") (pinfunction "G_1") (pintype "unspecified"))
      (node (ref "Q3") (pin "3") (pinfunction "D_3") (pintype "unspecified"))
      (node (ref "R10") (pin "1") (pinfunction "1_1") (pintype "input"))
      (node (ref "R13") (pin "2") (pinfunction "2_2") (pintype "input"))
    )
    (net (code "50") (name "Net-(U1-OSC_IN)") (class "Default")
      (node (ref "U1") (pin "12") (pinfunction "OSC_IN_12") (pintype "unspecified"))
      (node (ref "X1") (pin "2") (pinfunction "OSC2_2") (pintype "input"))
    )
    (net (code "51") (name "Net-(U1-OSC_OUT)") (class "Default")
      (node (ref "U1") (pin "13") (pinfunction "OSC_OUT_13") (pintype "unspecified"))
      (node (ref "X1") (pin "1") (pinfunction "OSC1_1") (pintype "input"))
    )
    (net (code "52") (name "POWER_LED") (class "Default")
      (node (ref "R3") (pin "2") (pinfunction "2_2") (pintype "input"))
      (node (ref "U1") (pin "95") (pinfunction "PB8_95") (pintype "unspecified"))
    )
    (net (code "53") (name "SENSE_V5") (class "Default")
      (node (ref "R14") (pin "1") (pinfunction "1_1") (pintype "input"))
      (node (ref "R15") (pin "2") (pinfunction "2_2") (pintype "input"))
      (node (ref "U1") (pin "35") (pinfunction "PB0_35") (pintype "unspecified"))
    )
    (net (code "54") (name "SOCKET_A0") (class "Default")
      (node (ref "H1L") (pin "9") (pinfunction "9_9") (pintype "unspecified"))
      (node (ref "H4R") (pin "20") (pinfunction "20_20") (pintype "unspecified"))
      (node (ref "H5R") (pin "20") (pinfunction "20_20") (pintype "unspecified"))
      (node (ref "U1") (pin "15") (pinfunction "PC0_15") (pintype "unspecified"))
      (node (ref "U2") (pin "25") (pinfunction "A0_25") (pintype "unspecified"))
      (node (ref "U3") (pin "25") (pinfunction "A0_25") (pintype "unspecified"))
    )
    (net (code "55") (name "SOCKET_A1") (class "Default")
      (node (ref "H1L") (pin "8") (pinfunction "8_8") (pintype "unspecified"))
      (node (ref "H4R") (pin "19") (pinfunction "19_19") (pintype "unspecified"))
      (node (ref "H5R") (pin "19") (pinfunction "19_19") (pintype "unspecified"))
      (node (ref "U1") (pin "16") (pinfunction "PC1_16") (pintype "unspecified"))
      (node (ref "U2") (pin "24") (pinfunction "A1_24") (pintype "unspecified"))
      (node (ref "U3") (pin "24") (pinfunction "A1_24") (pintype "unspecified"))
    )
    (net (code "56") (name "SOCKET_A2") (class "Default")
      (node (ref "H1L") (pin "7") (pinfunction "7_7") (pintype "unspecified"))
      (node (ref "H4R") (pin "18") (pinfunction "18_18") (pintype "unspecified"))
      (node (ref "H5R") (pin "18") (pinfunction "18_18") (pintype "unspecified"))
      (node (ref "U1") (pin "17") (pinfunction "PC2_17") (pintype "unspecified"))
      (node (ref "U2") (pin "23") (pinfunction "A2_23") (pintype "unspecified"))
      (node (ref "U3") (pin "23") (pinfunction "A2_23") (pintype "unspecified"))
    )
    (net (code "57") (name "SOCKET_A3") (class "Default")
      (node (ref "H1L") (pin "6") (pinfunction "6_6") (pintype "unspecified"))
      (node (ref "H4R") (pin "17") (pinfunction "17_17") (pintype "unspecified"))
      (node (ref "H5R") (pin "17") (pinfunction "17_17") (pintype "unspecified"))
      (node (ref "U1") (pin "18") (pinfunction "PC3_18") (pintype "unspecified"))
      (node (ref "U2") (pin "22") (pinfunction "A3_22") (pintype "unspecified"))
      (node (ref "U3") (pin "22") (pinfunction "A3_22") (pintype "unspecified"))
    )
    (net (code "58") (name "SOCKET_A4") (class "Default")
      (node (ref "H1L") (pin "5") (pinfunction "5_5") (pintype "unspecified"))
      (node (ref "H4R") (pin "16") (pinfunction "16_16") (pintype "unspecified"))
      (node (ref "H5R") (pin "16") (pinfunction "16_16") (pintype "unspecified"))
      (node (ref "U1") (pin "33") (pinfunction "PC4_33") (pintype "unspecified"))
      (node (ref "U2") (pin "21") (pinfunction "A4_21") (pintype "unspecified"))
      (node (ref "U3") (pin "21") (pinfunction "A4_21") (pintype "unspecified"))
    )
    (net (code "59") (name "SOCKET_A5") (class "Default")
      (node (ref "H1L") (pin "4") (pinfunction "4_4") (pintype "unspecified"))
      (node (ref "H4R") (pin "15") (pinfunction "15_15") (pintype "unspecified"))
      (node (ref "H5R") (pin "15") (pinfunction "15_15") (pintype "unspecified"))
      (node (ref "U1") (pin "34") (pinfunction "PC5_34") (pintype "unspecified"))
      (node (ref "U2") (pin "20") (pinfunction "A5_20") (pintype "unspecified"))
      (node (ref "U3") (pin "20") (pinfunction "A5_20") (pintype "unspecified"))
    )
    (net (code "60") (name "SOCKET_A6") (class "Default")
      (node (ref "H1L") (pin "3") (pinfunction "3_3") (pintype "unspecified"))
      (node (ref "H4R") (pin "14") (pinfunction "14_14") (pintype "unspecified"))
      (node (ref "H5R") (pin "14") (pinfunction "14_14") (pintype "unspecified"))
      (node (ref "U1") (pin "63") (pinfunction "PC6_63") (pintype "unspecified"))
      (node (ref "U2") (pin "19") (pinfunction "A6_19") (pintype "unspecified"))
      (node (ref "U3") (pin "19") (pinfunction "A6_19") (pintype "unspecified"))
    )
    (net (code "61") (name "SOCKET_A7") (class "Default")
      (node (ref "H1L") (pin "2") (pinfunction "2_2") (pintype "unspecified"))
      (node (ref "H4R") (pin "13") (pinfunction "13_13") (pintype "unspecified"))
      (node (ref "H5R") (pin "13") (pinfunction "13_13") (pintype "unspecified"))
      (node (ref "U1") (pin "64") (pinfunction "PC7_64") (pintype "unspecified"))
      (node (ref "U2") (pin "18") (pinfunction "A7_18") (pintype "unspecified"))
      (node (ref "U3") (pin "18") (pinfunction "A7_18") (pintype "unspecified"))
    )
    (net (code "62") (name "SOCKET_A8") (class "Default")
      (node (ref "H1R") (pin "1") (pinfunction "1_1") (pintype "unspecified"))
      (node (ref "H4R") (pin "12") (pinfunction "12_12") (pintype "unspecified"))
      (node (ref "H5R") (pin "12") (pinfunction "12_12") (pintype "unspecified"))
      (node (ref "U1") (pin "65") (pinfunction "PC8_65") (pintype "unspecified"))
      (node (ref "U2") (pin "8") (pinfunction "A8_8") (pintype "unspecified"))
      (node (ref "U3") (pin "8") (pinfunction "A8_8") (pintype "unspecified"))
    )
    (net (code "63") (name "SOCKET_A9") (class "Default")
      (node (ref "H1R") (pin "2") (pinfunction "2_2") (pintype "unspecified"))
      (node (ref "H4R") (pin "10") (pinfunction "10_10") (pintype "unspecified"))
      (node (ref "H5R") (pin "10") (pinfunction "10_10") (pintype "unspecified"))
      (node (ref "U1") (pin "66") (pinfunction "PC9_66") (pintype "unspecified"))
      (node (ref "U2") (pin "7") (pinfunction "A9_7") (pintype "unspecified"))
      (node (ref "U3") (pin "7") (pinfunction "A9_7") (pintype "unspecified"))
    )
    (net (code "64") (name "SOCKET_A10") (class "Default")
      (node (ref "H1R") (pin "3") (pinfunction "3_3") (pintype "unspecified"))
      (node (ref "H4R") (pin "9") (pinfunction "9_9") (pintype "unspecified"))
      (node (ref "H5R") (pin "9") (pinfunction "9_9") (pintype "unspecified"))
      (node (ref "U1") (pin "78") (pinfunction "PC10_78") (pintype "unspecified"))
      (node (ref "U2") (pin "6") (pinfunction "A10_6") (pintype "unspecified"))
      (node (ref "U3") (pin "6") (pinfunction "A10_6") (pintype "unspecified"))
    )
    (net (code "65") (name "SOCKET_A11") (class "Default")
      (node (ref "H1R") (pin "4") (pinfunction "4_4") (pintype "unspecified"))
      (node (ref "H4R") (pin "8") (pinfunction "8_8") (pintype "unspecified"))
      (node (ref "H5R") (pin "8") (pinfunction "8_8") (pintype "unspecified"))
      (node (ref "U1") (pin "79") (pinfunction "PC11_79") (pintype "unspecified"))
      (node (ref "U2") (pin "5") (pinfunction "A11_5") (pintype "unspecified"))
      (node (ref "U3") (pin "5") (pinfunction "A11_5") (pintype "unspecified"))
    )
    (net (code "66") (name "SOCKET_A12") (class "Default")
      (node (ref "H1R") (pin "5") (pinfunction "5_5") (pintype "unspecified"))
      (node (ref "H4R") (pin "7") (pinfunction "7_7") (pintype "unspecified"))
      (node (ref "H5R") (pin "7") (pinfunction "7_7") (pintype "unspecified"))
      (node (ref "U1") (pin "80") (pinfunction "PC12_80") (pintype "unspecified"))
      (node (ref "U2") (pin "4") (pinfunction "A12_4") (pintype "unspecified"))
      (node (ref "U3") (pin "4") (pinfunction "A12_4") (pintype "unspecified"))
    )
    (net (code "67") (name "SOCKET_A13") (class "Default")
      (node (ref "H1R") (pin "6") (pinfunction "6_6") (pintype "unspecified"))
      (node (ref "H4R") (pin "6") (pinfunction "6_6") (pintype "unspecified"))
      (node (ref "H5R") (pin "6") (pinfunction "6_6") (pintype "unspecified"))
      (node (ref "U1") (pin "24") (pinfunction "PA1_24") (pintype "unspecified"))
      (node (ref "U1") (pin "7") (pinfunction "PC13-TAMPER-RTC_7") (pintype "unspecified"))
      (node (ref "U2") (pin "3") (pinfunction "A13_3") (pintype "unspecified"))
      (node (ref "U3") (pin "3") (pinfunction "A13_3") (pintype "unspecified"))
    )
    (net (code "68") (name "SOCKET_A14") (class "Default")
      (node (ref "H1R") (pin "7") (pinfunction "7_7") (pintype "unspecified"))
      (node (ref "H4R") (pin "5") (pinfunction "5_5") (pintype "unspecified"))
      (node (ref "H5R") (pin "5") (pinfunction "5_5") (pintype "unspecified"))
      (node (ref "U1") (pin "25") (pinfunction "PA2_25") (pintype "unspecified"))
      (node (ref "U1") (pin "8") (pinfunction "PC14-OSC32_IN_8") (pintype "unspecified"))
      (node (ref "U2") (pin "2") (pinfunction "A14_2") (pintype "unspecified"))
      (node (ref "U3") (pin "2") (pinfunction "A14_2") (pintype "unspecified"))
    )
    (net (code "69") (name "SOCKET_A15") (class "Default")
      (node (ref "H1R") (pin "8") (pinfunction "8_8") (pintype "unspecified"))
      (node (ref "H4R") (pin "4") (pinfunction "4_4") (pintype "unspecified"))
      (node (ref "H5R") (pin "4") (pinfunction "4_4") (pintype "unspecified"))
      (node (ref "U1") (pin "26") (pinfunction "PA3_26") (pintype "unspecified"))
      (node (ref "U1") (pin "9") (pinfunction "PC15-OSC32_OUT_9") (pintype "unspecified"))
      (node (ref "U2") (pin "1") (pinfunction "A15_1") (pintype "unspecified"))
      (node (ref "U3") (pin "1") (pinfunction "A15_1") (pintype "unspecified"))
    )
    (net (code "70") (name "SOCKET_A16") (class "Default")
      (node (ref "H1R") (pin "9") (pinfunction "9_9") (pintype "unspecified"))
      (node (ref "H4R") (pin "3") (pinfunction "3_3") (pintype "unspecified"))
      (node (ref "H5R") (pin "3") (pinfunction "3_3") (pintype "unspecified"))
      (node (ref "U1") (pin "29") (pinfunction "PA4_29") (pintype "unspecified"))
      (node (ref "U2") (pin "48") (pinfunction "A16_48") (pintype "unspecified"))
      (node (ref "U3") (pin "48") (pinfunction "A16_48") (pintype "unspecified"))
    )
    (net (code "71") (name "SOCKET_A17") (class "Default")
      (node (ref "H1L") (pin "1") (pinfunction "1_1") (pintype "unspecified"))
      (node (ref "H4R") (pin "2") (pinfunction "2_2") (pintype "unspecified"))
      (node (ref "H9") (pin "1") (pinfunction "1_1") (pintype "input"))
      (node (ref "R16") (pin "2") (pinfunction "2_2") (pintype "input"))
    )
    (net (code "72") (name "SOCKET_A18") (class "Default")
      (node (ref "H7") (pin "1") (pinfunction "1_1") (pintype "unspecified"))
      (node (ref "R9") (pin "2") (pinfunction "2_2") (pintype "input"))
    )
    (net (code "73") (name "SOCKET_A19") (class "Default")
      (node (ref "H8") (pin "1") (pinfunction "1_1") (pintype "unspecified"))
      (node (ref "R8") (pin "2") (pinfunction "2_2") (pintype "input"))
    )
    (net (code "74") (name "SOCKET_D0") (class "Default")
      (node (ref "H1L") (pin "13") (pinfunction "13_13") (pintype "unspecified"))
      (node (ref "H3L") (pin "19") (pinfunction "19_19") (pintype "unspecified"))
      (node (ref "H7L") (pin "19") (pinfunction "19_19") (pintype "unspecified"))
      (node (ref "U5") (pin "23") (pinfunction "4Y4_23") (pintype "unspecified"))
    )
    (net (code "75") (name "SOCKET_D1") (class "Default")
      (node (ref "H1L") (pin "15") (pinfunction "15_15") (pintype "unspecified"))
      (node (ref "H3L") (pin "18") (pinfunction "18_18") (pintype "unspecified"))
      (node (ref "H7L") (pin "18") (pinfunction "18_18") (pintype "unspecified"))
      (node (ref "U5") (pin "22") (pinfunction "4Y3_22") (pintype "unspecified"))
    )
    (net (code "76") (name "SOCKET_D2") (class "Default")
      (node (ref "H1L") (pin "17") (pinfunction "17_17") (pintype "unspecified"))
      (node (ref "H3L") (pin "17") (pinfunction "17_17") (pintype "unspecified"))
      (node (ref "H7L") (pin "17") (pinfunction "17_17") (pintype "unspecified"))
      (node (ref "U5") (pin "20") (pinfunction "4Y2_20") (pintype "unspecified"))
    )
    (net (code "77") (name "SOCKET_D3") (class "Default")
      (node (ref "H1L") (pin "19") (pinfunction "19_19") (pintype "unspecified"))
      (node (ref "H3L") (pin "16") (pinfunction "16_16") (pintype "unspecified"))
      (node (ref "H7L") (pin "16") (pinfunction "16_16") (pintype "unspecified"))
      (node (ref "U5") (pin "19") (pinfunction "4Y1_19") (pintype "unspecified"))
    )
    (net (code "78") (name "SOCKET_D4") (class "Default")
      (node (ref "H1R") (pin "19") (pinfunction "19_19") (pintype "unspecified"))
      (node (ref "H3L") (pin "15") (pinfunction "15_15") (pintype "unspecified"))
      (node (ref "H7L") (pin "15") (pinfunction "15_15") (pintype "unspecified"))
      (node (ref "U5") (pin "17") (pinfunction "3Y4_17") (pintype "unspecified"))
    )
    (net (code "79") (name "SOCKET_D5") (class "Default")
      (node (ref "H1R") (pin "17") (pinfunction "17_17") (pintype "unspecified"))
      (node (ref "H3L") (pin "14") (pinfunction "14_14") (pintype "unspecified"))
      (node (ref "H7L") (pin "14") (pinfunction "14_14") (pintype "unspecified"))
      (node (ref "U5") (pin "16") (pinfunction "3Y3_16") (pintype "unspecified"))
    )
    (net (code "80") (name "SOCKET_D6") (class "Default")
      (node (ref "H1R") (pin "15") (pinfunction "15_15") (pintype "unspecified"))
      (node (ref "H3L") (pin "13") (pinfunction "13_13") (pintype "unspecified"))
      (node (ref "H7L") (pin "13") (pinfunction "13_13") (pintype "unspecified"))
      (node (ref "U5") (pin "14") (pinfunction "3Y2_14") (pintype "unspecified"))
    )
    (net (code "81") (name "SOCKET_D7") (class "Default")
      (node (ref "H1R") (pin "13") (pinfunction "13_13") (pintype "unspecified"))
      (node (ref "H3L") (pin "12") (pinfunction "12_12") (pintype "unspecified"))
      (node (ref "H7L") (pin "12") (pinfunction "12_12") (pintype "unspecified"))
      (node (ref "U5") (pin "13") (pinfunction "3Y1_13") (pintype "unspecified"))
    )
    (net (code "82") (name "SOCKET_D8") (class "Default")
      (node (ref "H1L") (pin "14") (pinfunction "14_14") (pintype "unspecified"))
      (node (ref "H3L") (pin "10") (pinfunction "10_10") (pintype "unspecified"))
      (node (ref "H7L") (pin "10") (pinfunction "10_10") (pintype "unspecified"))
      (node (ref "U5") (pin "12") (pinfunction "2Y4_12") (pintype "unspecified"))
    )
    (net (code "83") (name "SOCKET_D9") (class "Default")
      (node (ref "H1L") (pin "16") (pinfunction "16_16") (pintype "unspecified"))
      (node (ref "H3L") (pin "9") (pinfunction "9_9") (pintype "unspecified"))
      (node (ref "H7L") (pin "9") (pinfunction "9_9") (pintype "unspecified"))
      (node (ref "U5") (pin "11") (pinfunction "2Y3_11") (pintype "unspecified"))
    )
    (net (code "84") (name "SOCKET_D10") (class "Default")
      (node (ref "H1L") (pin "18") (pinfunction "18_18") (pintype "unspecified"))
      (node (ref "H3L") (pin "8") (pinfunction "8_8") (pintype "unspecified"))
      (node (ref "H7L") (pin "8") (pinfunction "8_8") (pintype "unspecified"))
      (node (ref "U5") (pin "9") (pinfunction "2Y2_9") (pintype "unspecified"))
    )
    (net (code "85") (name "SOCKET_D11") (class "Default")
      (node (ref "H1L") (pin "20") (pinfunction "20_20") (pintype "unspecified"))
      (node (ref "H3L") (pin "7") (pinfunction "7_7") (pintype "unspecified"))
      (node (ref "H7L") (pin "7") (pinfunction "7_7") (pintype "unspecified"))
      (node (ref "U5") (pin "8") (pinfunction "2Y1_8") (pintype "unspecified"))
    )
    (net (code "86") (name "SOCKET_D12") (class "Default")
      (node (ref "H1R") (pin "18") (pinfunction "18_18") (pintype "unspecified"))
      (node (ref "H3L") (pin "6") (pinfunction "6_6") (pintype "unspecified"))
      (node (ref "H7L") (pin "6") (pinfunction "6_6") (pintype "unspecified"))
      (node (ref "U5") (pin "6") (pinfunction "1Y4_6") (pintype "unspecified"))
    )
    (net (code "87") (name "SOCKET_D13") (class "Default")
      (node (ref "H1R") (pin "16") (pinfunction "16_16") (pintype "unspecified"))
      (node (ref "H3L") (pin "5") (pinfunction "5_5") (pintype "unspecified"))
      (node (ref "H7L") (pin "5") (pinfunction "5_5") (pintype "unspecified"))
      (node (ref "U5") (pin "5") (pinfunction "1Y3_5") (pintype "unspecified"))
    )
    (net (code "88") (name "SOCKET_D14") (class "Default")
      (node (ref "H1R") (pin "14") (pinfunction "14_14") (pintype "unspecified"))
      (node (ref "H3L") (pin "4") (pinfunction "4_4") (pintype "unspecified"))
      (node (ref "H7L") (pin "4") (pinfunction "4_4") (pintype "unspecified"))
      (node (ref "U5") (pin "3") (pinfunction "1Y2_3") (pintype "unspecified"))
    )
    (net (code "89") (name "SOCKET_D15") (class "Default")
      (node (ref "H1R") (pin "12") (pinfunction "12_12") (pintype "unspecified"))
      (node (ref "H3L") (pin "3") (pinfunction "3_3") (pintype "unspecified"))
      (node (ref "H7L") (pin "3") (pinfunction "3_3") (pintype "unspecified"))
      (node (ref "U5") (pin "2") (pinfunction "1Y1_2") (pintype "unspecified"))
    )
    (net (code "90") (name "SOCKET_D16") (class "Default")
      (node (ref "H2L") (pin "2") (pinfunction "2_2") (pintype "unspecified"))
      (node (ref "H4L") (pin "19") (pinfunction "19_19") (pintype "unspecified"))
      (node (ref "H5L") (pin "19") (pinfunction "19_19") (pintype "unspecified"))
      (node (ref "U6") (pin "23") (pinfunction "4Y4_23") (pintype "unspecified"))
    )
    (net (code "91") (name "SOCKET_D17") (class "Default")
      (node (ref "H2L") (pin "4") (pinfunction "4_4") (pintype "unspecified"))
      (node (ref "H4L") (pin "18") (pinfunction "18_18") (pintype "unspecified"))
      (node (ref "H5L") (pin "18") (pinfunction "18_18") (pintype "unspecified"))
      (node (ref "U6") (pin "22") (pinfunction "4Y3_22") (pintype "unspecified"))
    )
    (net (code "92") (name "SOCKET_D18") (class "Default")
      (node (ref "H2L") (pin "6") (pinfunction "6_6") (pintype "unspecified"))
      (node (ref "H4L") (pin "17") (pinfunction "17_17") (pintype "unspecified"))
      (node (ref "H5L") (pin "17") (pinfunction "17_17") (pintype "unspecified"))
      (node (ref "U6") (pin "20") (pinfunction "4Y2_20") (pintype "unspecified"))
    )
    (net (code "93") (name "SOCKET_D19") (class "Default")
      (node (ref "H2L") (pin "8") (pinfunction "8_8") (pintype "unspecified"))
      (node (ref "H4L") (pin "16") (pinfunction "16_16") (pintype "unspecified"))
      (node (ref "H5L") (pin "16") (pinfunction "16_16") (pintype "unspecified"))
      (node (ref "U6") (pin "19") (pinfunction "4Y1_19") (pintype "unspecified"))
    )
    (net (code "94") (name "SOCKET_D20") (class "Default")
      (node (ref "H2R") (pin "8") (pinfunction "8_8") (pintype "unspecified"))
      (node (ref "H4L") (pin "15") (pinfunction "15_15") (pintype "unspecified"))
      (node (ref "H5L") (pin "15") (pinfunction "15_15") (pintype "unspecified"))
      (node (ref "U6") (pin "17") (pinfunction "3Y4_17") (pintype "unspecified"))
    )
    (net (code "95") (name "SOCKET_D21") (class "Default")
      (node (ref "H2R") (pin "6") (pinfunction "6_6") (pintype "unspecified"))
      (node (ref "H4L") (pin "14") (pinfunction "14_14") (pintype "unspecified"))
      (node (ref "H5L") (pin "14") (pinfunction "14_14") (pintype "unspecified"))
      (node (ref "U6") (pin "16") (pinfunction "3Y3_16") (pintype "unspecified"))
    )
    (net (code "96") (name "SOCKET_D22") (class "Default")
      (node (ref "H2R") (pin "4") (pinfunction "4_4") (pintype "unspecified"))
      (node (ref "H4L") (pin "13") (pinfunction "13_13") (pintype "unspecified"))
      (node (ref "H5L") (pin "13") (pinfunction "13_13") (pintype "unspecified"))
      (node (ref "U6") (pin "14") (pinfunction "3Y2_14") (pintype "unspecified"))
    )
    (net (code "97") (name "SOCKET_D23") (class "Default")
      (node (ref "H2R") (pin "2") (pinfunction "2_2") (pintype "unspecified"))
      (node (ref "H4L") (pin "12") (pinfunction "12_12") (pintype "unspecified"))
      (node (ref "H5L") (pin "12") (pinfunction "12_12") (pintype "unspecified"))
      (node (ref "U6") (pin "13") (pinfunction "3Y1_13") (pintype "unspecified"))
    )
    (net (code "98") (name "SOCKET_D24") (class "Default")
      (node (ref "H2L") (pin "3") (pinfunction "3_3") (pintype "unspecified"))
      (node (ref "H4L") (pin "10") (pinfunction "10_10") (pintype "unspecified"))
      (node (ref "H5L") (pin "10") (pinfunction "10_10") (pintype "unspecified"))
      (node (ref "U6") (pin "12") (pinfunction "2Y4_12") (pintype "unspecified"))
    )
    (net (code "99") (name "SOCKET_D25") (class "Default")
      (node (ref "H2L") (pin "5") (pinfunction "5_5") (pintype "unspecified"))
      (node (ref "H4L") (pin "9") (pinfunction "9_9") (pintype "unspecified"))
      (node (ref "H5L") (pin "9") (pinfunction "9_9") (pintype "unspecified"))
      (node (ref "U6") (pin "11") (pinfunction "2Y3_11") (pintype "unspecified"))
    )
    (net (code "100") (name "SOCKET_D26") (class "Default")
      (node (ref "H2L") (pin "7") (pinfunction "7_7") (pintype "unspecified"))
      (node (ref "H4L") (pin "8") (pinfunction "8_8") (pintype "unspecified"))
      (node (ref "H5L") (pin "8") (pinfunction "8_8") (pintype "unspecified"))
      (node (ref "U6") (pin "9") (pinfunction "2Y2_9") (pintype "unspecified"))
    )
    (net (code "101") (name "SOCKET_D27") (class "Default")
      (node (ref "H2L") (pin "9") (pinfunction "9_9") (pintype "unspecified"))
      (node (ref "H4L") (pin "7") (pinfunction "7_7") (pintype "unspecified"))
      (node (ref "H5L") (pin "7") (pinfunction "7_7") (pintype "unspecified"))
      (node (ref "U6") (pin "8") (pinfunction "2Y1_8") (pintype "unspecified"))
    )
    (net (code "102") (name "SOCKET_D28") (class "Default")
      (node (ref "H2R") (pin "7") (pinfunction "7_7") (pintype "unspecified"))
      (node (ref "H4L") (pin "6") (pinfunction "6_6") (pintype "unspecified"))
      (node (ref "H5L") (pin "6") (pinfunction "6_6") (pintype "unspecified"))
      (node (ref "U6") (pin "6") (pinfunction "1Y4_6") (pintype "unspecified"))
    )
    (net (code "103") (name "SOCKET_D29") (class "Default")
      (node (ref "H2R") (pin "5") (pinfunction "5_5") (pintype "unspecified"))
      (node (ref "H4L") (pin "5") (pinfunction "5_5") (pintype "unspecified"))
      (node (ref "H5L") (pin "5") (pinfunction "5_5") (pintype "unspecified"))
      (node (ref "U6") (pin "5") (pinfunction "1Y3_5") (pintype "unspecified"))
    )
    (net (code "104") (name "SOCKET_D30") (class "Default")
      (node (ref "H2R") (pin "3") (pinfunction "3_3") (pintype "unspecified"))
      (node (ref "H4L") (pin "4") (pinfunction "4_4") (pintype "unspecified"))
      (node (ref "H5L") (pin "4") (pinfunction "4_4") (pintype "unspecified"))
      (node (ref "U6") (pin "3") (pinfunction "1Y2_3") (pintype "unspecified"))
    )
    (net (code "105") (name "SOCKET_D31") (class "Default")
      (node (ref "H2R") (pin "1") (pinfunction "1_1") (pintype "unspecified"))
      (node (ref "H4L") (pin "3") (pinfunction "3_3") (pintype "unspecified"))
      (node (ref "H5L") (pin "3") (pinfunction "3_3") (pintype "unspecified"))
      (node (ref "U1") (pin "51") (pinfunction "PB12_51") (pintype "unspecified"))
      (node (ref "U6") (pin "2") (pinfunction "1Y1_2") (pintype "unspecified"))
    )
    (net (code "106") (name "SOCKET_OE") (class "Default")
      (node (ref "Q1") (pin "1") (pinfunction "G_1") (pintype "unspecified"))
      (node (ref "Q3") (pin "1") (pinfunction "G_1") (pintype "unspecified"))
      (node (ref "R17") (pin "2") (pinfunction "2_2") (pintype "input"))
      (node (ref "R7") (pin "1") (pinfunction "1_1") (pintype "input"))
      (node (ref "U1") (pin "23") (pinfunction "PA0-WKUP_23") (pintype "unspecified"))
      (node (ref "U5") (pin "1") (pinfunction "1OE#_1") (pintype "unspecified"))
      (node (ref "U5") (pin "24") (pinfunction "4OE#_24") (pintype "unspecified"))
      (node (ref "U5") (pin "25") (pinfunction "3OE#_25") (pintype "unspecified"))
      (node (ref "U5") (pin "48") (pinfunction "2OE#_48") (pintype "unspecified"))
      (node (ref "U6") (pin "1") (pinfunction "1OE#_1") (pintype "unspecified"))
      (node (ref "U6") (pin "24") (pinfunction "4OE#_24") (pintype "unspecified"))
      (node (ref "U6") (pin "25") (pinfunction "3OE#_25") (pintype "unspecified"))
      (node (ref "U6") (pin "48") (pinfunction "2OE#_48") (pintype "unspecified"))
    )
    (net (code "107") (name "SOCKET_OE_EXT") (class "Default")
      (node (ref "H1L") (pin "12") (pinfunction "12_12") (pintype "unspecified"))
      (node (ref "H3L") (pin "20") (pinfunction "20_20") (pintype "unspecified"))
      (node (ref "H5L") (pin "20") (pinfunction "20_20") (pintype "unspecified"))
      (node (ref "H7L") (pin "20") (pinfunction "20_20") (pintype "unspecified"))
      (node (ref "R17") (pin "1") (pinfunction "1_1") (pintype "input"))
    )
    (net (code "108") (name "SOCKET_V5") (class "Default")
      (node (ref "D2") (pin "2") (pinfunction "+_2") (pintype "unspecified"))
      (node (ref "H1R") (pin "20") (pinfunction "20_20") (pintype "unspecified"))
      (node (ref "H2R") (pin "9") (pinfunction "9_9") (pintype "unspecified"))
      (node (ref "H4R") (pin "1") (pinfunction "1_1") (pintype "unspecified"))
      (node (ref "H5R") (pin "1") (pinfunction "1_1") (pintype "unspecified"))
      (node (ref "R14") (pin "2") (pinfunction "2_2") (pintype "input"))
    )
    (net (code "109") (name "STM_BOOT0") (class "Default")
      (node (ref "H5") (pin "1") (pinfunction "1_1") (pintype "unspecified"))
      (node (ref "R6") (pin "1") (pinfunction "1_1") (pintype "input"))
      (node (ref "U1") (pin "91") (pinfunction "PB5_91") (pintype "unspecified"))
      (node (ref "U1") (pin "94") (pinfunction "BOOT0_94") (pintype "unspecified"))
    )
    (net (code "110") (name "STM_NRST") (class "Default")
      (node (ref "H6") (pin "5") (pinfunction "5_5") (pintype "input"))
      (node (ref "U1") (pin "14") (pinfunction "NRST_14") (pintype "unspecified"))
    )
    (net (code "111") (name "STM_SWCLK_TCK") (class "Default")
      (node (ref "H6") (pin "2") (pinfunction "2_2") (pintype "input"))
      (node (ref "U1") (pin "76") (pinfunction "PA14_76") (pintype "unspecified"))
    )
    (net (code "112") (name "STM_SWDIO_TMS") (class "Default")
      (node (ref "H6") (pin "4") (pinfunction "4_4") (pintype "input"))
      (node (ref "U1") (pin "72") (pinfunction "PA13_72") (pintype "unspecified"))
    )
    (net (code "113") (name "STM_SWO_TDO") (class "Default")
      (node (ref "H6") (pin "6") (pinfunction "6_6") (pintype "input"))
      (node (ref "U1") (pin "89") (pinfunction "PB3_89") (pintype "unspecified"))
    )
    (net (code "114") (name "USB_CC1") (class "Default")
      (node (ref "R5") (pin "1") (pinfunction "1_1") (pintype "input"))
      (node (ref "U1") (pin "67") (pinfunction "PA8_67") (pintype "unspecified"))
      (node (ref "USB1") (pin "A5") (pinfunction "CC1_A5") (pintype "unspecified"))
      (node (ref "USBC1") (pin "A5") (pinfunction "CC1_A5") (pintype "unspecified"))
    )
    (net (code "115") (name "USB_CC2") (class "Default")
      (node (ref "R4") (pin "1") (pinfunction "1_1") (pintype "input"))
      (node (ref "U1") (pin "69") (pinfunction "PA10_69") (pintype "unspecified"))
      (node (ref "USB1") (pin "B5") (pinfunction "CC2_B5") (pintype "unspecified"))
      (node (ref "USBC1") (pin "B5") (pinfunction "CC2_B5") (pintype "unspecified"))
    )
    (net (code "116") (name "USB_DM") (class "Default")
      (node (ref "U1") (pin "70") (pinfunction "PA11_70") (pintype "unspecified"))
      (node (ref "USB1") (pin "A7") (pinfunction "D-_A7") (pintype "unspecified"))
      (node (ref "USB1") (pin "B7") (pinfunction "D-_B7") (pintype "unspecified"))
      (node (ref "USBC1") (pin "A7") (pinfunction "DN1_A7") (pintype "unspecified"))
      (node (ref "USBC1") (pin "B7") (pinfunction "DN2_B7") (pintype "unspecified"))
    )
    (net (code "117") (name "USB_DP") (class "Default")
      (node (ref "U1") (pin "71") (pinfunction "PA12_71") (pintype "unspecified"))
      (node (ref "USB1") (pin "A6") (pinfunction "D+_A6") (pintype "unspecified"))
      (node (ref "USB1") (pin "B6") (pinfunction "D+_B6") (pintype "unspecified"))
      (node (ref "USBC1") (pin "A6") (pinfunction "DP1_A6") (pintype "unspecified"))
      (node (ref "USBC1") (pin "B6") (pinfunction "DP2_B6") (pintype "unspecified"))
    )
    (net (code "118") (name "USB_V5") (class "Default")
      (node (ref "D1") (pin "2") (pinfunction "+_2") (pintype "unspecified"))
      (node (ref "U1") (pin "68") (pinfunction "PA9_68") (pintype "unspecified"))
      (node (ref "USB1") (pin "A4") (pinfunction "VBUS_A4") (pintype "unspecified"))
      (node (ref "USB1") (pin "A9") (pinfunction "VBUS_A9") (pintype "unspecified"))
      (node (ref "USB1") (pin "B4") (pinfunction "VBUS_B4") (pintype "unspecified"))
      (node (ref "USB1") (pin "B9") (pinfunction "VBUS_B9") (pintype "unspecified"))
      (node (ref "USBC1") (pin "A4B9") (pinfunction "VBUS_A4B9") (pintype "unspecified"))
      (node (ref "USBC1") (pin "B4A9") (pinfunction "VBUS_B4A9") (pintype "unspecified"))
    )
    (net (code "119") (name "V3P3") (class "Default")
      (node (ref "C4") (pin "1") (pinfunction "1_1") (pintype "input"))
      (node (ref "C5") (pin "2") (pinfunction "2_2") (pintype "unspecified"))
      (node (ref "C6") (pin "1") (pinfunction "1_1") (pintype "input"))
      (node (ref "C7") (pin "1") (pinfunction "1_1") (pintype "input"))
      (node (ref "C8") (pin "1") (pinfunction "1_1") (pintype "input"))
      (node (ref "H6") (pin "1") (pinfunction "1_1") (pintype "input"))
      (node (ref "U1") (pin "100") (pinfunction "VDD_3_100") (pintype "unspecified"))
      (node (ref "U1") (pin "11") (pinfunction "VDD_5_11") (pintype "unspecified"))
      (node (ref "U1") (pin "21") (pinfunction "VREF+_21") (pintype "unspecified"))
      (node (ref "U1") (pin "22") (pinfunction "VDDA_22") (pintype "unspecified"))
      (node (ref "U1") (pin "28") (pinfunction "VDD_4_28") (pintype "unspecified"))
      (node (ref "U1") (pin "50") (pinfunction "VDD_1_50") (pintype "unspecified"))
      (node (ref "U1") (pin "6") (pinfunction "VBAT_6") (pintype "unspecified"))
      (node (ref "U1") (pin "75") (pinfunction "VDD_2_75") (pintype "unspecified"))
      (node (ref "U4") (pin "2") (pinfunction "Vout_2") (pintype "unspecified"))
      (node (ref "U4") (pin "4") (pinfunction "Vout_4") (pintype "unspecified"))
    )
    (net (code "120") (name "V5") (class "Default")
      (node (ref "C1") (pin "1") (pinfunction "1_1") (pintype "input"))
      (node (ref "C2") (pin "1") (pinfunction "1_1") (pintype "input"))
      (node (ref "C3") (pin "2") (pinfunction "2_2") (pintype "unspecified"))
      (node (ref "D1") (pin "1") (pinfunction "-_1") (pintype "unspecified"))
      (node (ref "D2") (pin "1") (pinfunction "-_1") (pintype "unspecified"))
      (node (ref "LED3") (pin "2") (pinfunction "+_2") (pintype "unspecified"))
      (node (ref "Q1") (pin "2") (pinfunction "S_2") (pintype "unspecified"))
      (node (ref "R11") (pin "2") (pinfunction "2_2") (pintype "input"))
      (node (ref "R12") (pin "1") (pinfunction "1_1") (pintype "input"))
      (node (ref "U2") (pin "37") (pinfunction "VCC_37") (pintype "passive"))
      (node (ref "U2") (pin "47") (pinfunction "BYTE_47") (pintype "unspecified"))
      (node (ref "U3") (pin "37") (pinfunction "VCC_37") (pintype "passive"))
      (node (ref "U3") (pin "47") (pinfunction "BYTE_47") (pintype "unspecified"))
      (node (ref "U4") (pin "3") (pinfunction "Vin_3") (pintype "unspecified"))
      (node (ref "U5") (pin "18") (pinfunction "VCC_18") (pintype "unspecified"))
      (node (ref "U5") (pin "31") (pinfunction "VCC_31") (pintype "unspecified"))
      (node (ref "U5") (pin "42") (pinfunction "VCC_42") (pintype "unspecified"))
      (node (ref "U5") (pin "7") (pinfunction "VCC_7") (pintype "unspecified"))
      (node (ref "U6") (pin "18") (pinfunction "VCC_18") (pintype "unspecified"))
      (node (ref "U6") (pin "31") (pinfunction "VCC_31") (pintype "unspecified"))
      (node (ref "U6") (pin "42") (pinfunction "VCC_42") (pintype "unspecified"))
      (node (ref "U6") (pin "7") (pinfunction "VCC_7") (pintype "unspecified"))
    )
    (net (code "121") (name "unconnected-(H1L-Pad10)") (class "Default")
      (node (ref "H1L") (pin "10") (pinfunction "10_10") (pintype "unspecified+no_connect"))
    )
    (net (code "122") (name "unconnected-(H1R-Pad10)") (class "Default")
      (node (ref "H1R") (pin "10") (pinfunction "10_10") (pintype "unspecified+no_connect"))
    )
    (net (code "123") (name "unconnected-(H2L-Pad1)") (class "Default")
      (node (ref "H2L") (pin "1") (pinfunction "1_1") (pintype "unspecified+no_connect"))
    )
    (net (code "124") (name "unconnected-(H3L-Pad1)") (class "Default")
      (node (ref "H3L") (pin "1") (pinfunction "1_1") (pintype "unspecified+no_connect"))
    )
    (net (code "125") (name "unconnected-(H3L-Pad2)") (class "Default")
      (node (ref "H3L") (pin "2") (pinfunction "2_2") (pintype "unspecified+no_connect"))
    )
    (net (code "126") (name "unconnected-(H4L-Pad1)") (class "Default")
      (node (ref "H4L") (pin "1") (pinfunction "1_1") (pintype "unspecified+no_connect"))
    )
    (net (code "127") (name "unconnected-(H4L-Pad2)") (class "Default")
      (node (ref "H4L") (pin "2") (pinfunction "2_2") (pintype "unspecified+no_connect"))
    )
    (net (code "128") (name "unconnected-(H4L-Pad20)") (class "Default")
      (node (ref "H4L") (pin "20") (pinfunction "20_20") (pintype "unspecified+no_connect"))
    )
    (net (code "129") (name "unconnected-(H5L-Pad1)") (class "Default")
      (node (ref "H5L") (pin "1") (pinfunction "1_1") (pintype "unspecified+no_connect"))
    )
    (net (code "130") (name "unconnected-(H5L-Pad2)") (class "Default")
      (node (ref "H5L") (pin "2") (pinfunction "2_2") (pintype "unspecified+no_connect"))
    )
    (net (code "131") (name "unconnected-(H5R-Pad2)") (class "Default")
      (node (ref "H5R") (pin "2") (pinfunction "2_2") (pintype "unspecified+no_connect"))
    )
    (net (code "132") (name "unconnected-(H7L-Pad1)") (class "Default")
      (node (ref "H7L") (pin "1") (pinfunction "1_1") (pintype "unspecified+no_connect"))
    )
    (net (code "133") (name "unconnected-(H7L-Pad2)") (class "Default")
      (node (ref "H7L") (pin "2") (pinfunction "2_2") (pintype "unspecified+no_connect"))
    )
    (net (code "134") (name "unconnected-(U1-NC-Pad73)") (class "Default")
      (node (ref "U1") (pin "73") (pinfunction "NC_73") (pintype "unspecified+no_connect"))
    )
    (net (code "135") (name "unconnected-(U1-PA15-Pad77)") (class "Default")
      (node (ref "U1") (pin "77") (pinfunction "PA15_77") (pintype "unspecified+no_connect"))
    )
    (net (code "136") (name "unconnected-(U1-PB1-Pad36)") (class "Default")
      (node (ref "U1") (pin "36") (pinfunction "PB1_36") (pintype "unspecified+no_connect"))
    )
    (net (code "137") (name "unconnected-(U1-PB15-Pad54)") (class "Default")
      (node (ref "U1") (pin "54") (pinfunction "PB15_54") (pintype "unspecified+no_connect"))
    )
    (net (code "138") (name "unconnected-(U2-NC-Pad10)") (class "Default")
      (node (ref "U2") (pin "10") (pinfunction "NC_10") (pintype "unspecified+no_connect"))
    )
    (net (code "139") (name "unconnected-(U2-NC-Pad13)") (class "Default")
      (node (ref "U2") (pin "13") (pinfunction "NC_13") (pintype "unspecified+no_connect"))
    )
    (net (code "140") (name "unconnected-(U2-NC-Pad14)") (class "Default")
      (node (ref "U2") (pin "14") (pinfunction "NC_14") (pintype "unspecified+no_connect"))
    )
    (net (code "141") (name "unconnected-(U3-NC-Pad10)") (class "Default")
      (node (ref "U3") (pin "10") (pinfunction "NC_10") (pintype "unspecified+no_connect"))
    )
    (net (code "142") (name "unconnected-(U3-NC-Pad13)") (class "Default")
      (node (ref "U3") (pin "13") (pinfunction "NC_13") (pintype "unspecified+no_connect"))
    )
    (net (code "143") (name "unconnected-(U3-NC-Pad14)") (class "Default")
      (node (ref "U3") (pin "14") (pinfunction "NC_14") (pintype "unspecified+no_connect"))
    )
    (net (code "144") (name "unconnected-(USB1-SUB1-PadA8)") (class "Default")
      (node (ref "USB1") (pin "A8") (pinfunction "SUB1_A8") (pintype "unspecified+no_connect"))
    )
    (net (code "145") (name "unconnected-(USB1-SUB2-PadB8)") (class "Default")
      (node (ref "USB1") (pin "B8") (pinfunction "SUB2_B8") (pintype "unspecified+no_connect"))
    )
    (net (code "146") (name "unconnected-(USBC1-SBU1-PadA8)") (class "Default")
      (node (ref "USBC1") (pin "A8") (pinfunction "SBU1_A8") (pintype "unspecified+no_connect"))
    )
    (net (code "147") (name "unconnected-(USBC1-SBU2-PadB8)") (class "Default")
      (node (ref "USBC1") (pin "B8") (pinfunction "SBU2_B8") (pintype "unspecified+no_connect"))
    )
  )
)
